# Attenuverting_LinExp_VCA.net
KiCad netlist of a schematic drawn in EAGLE
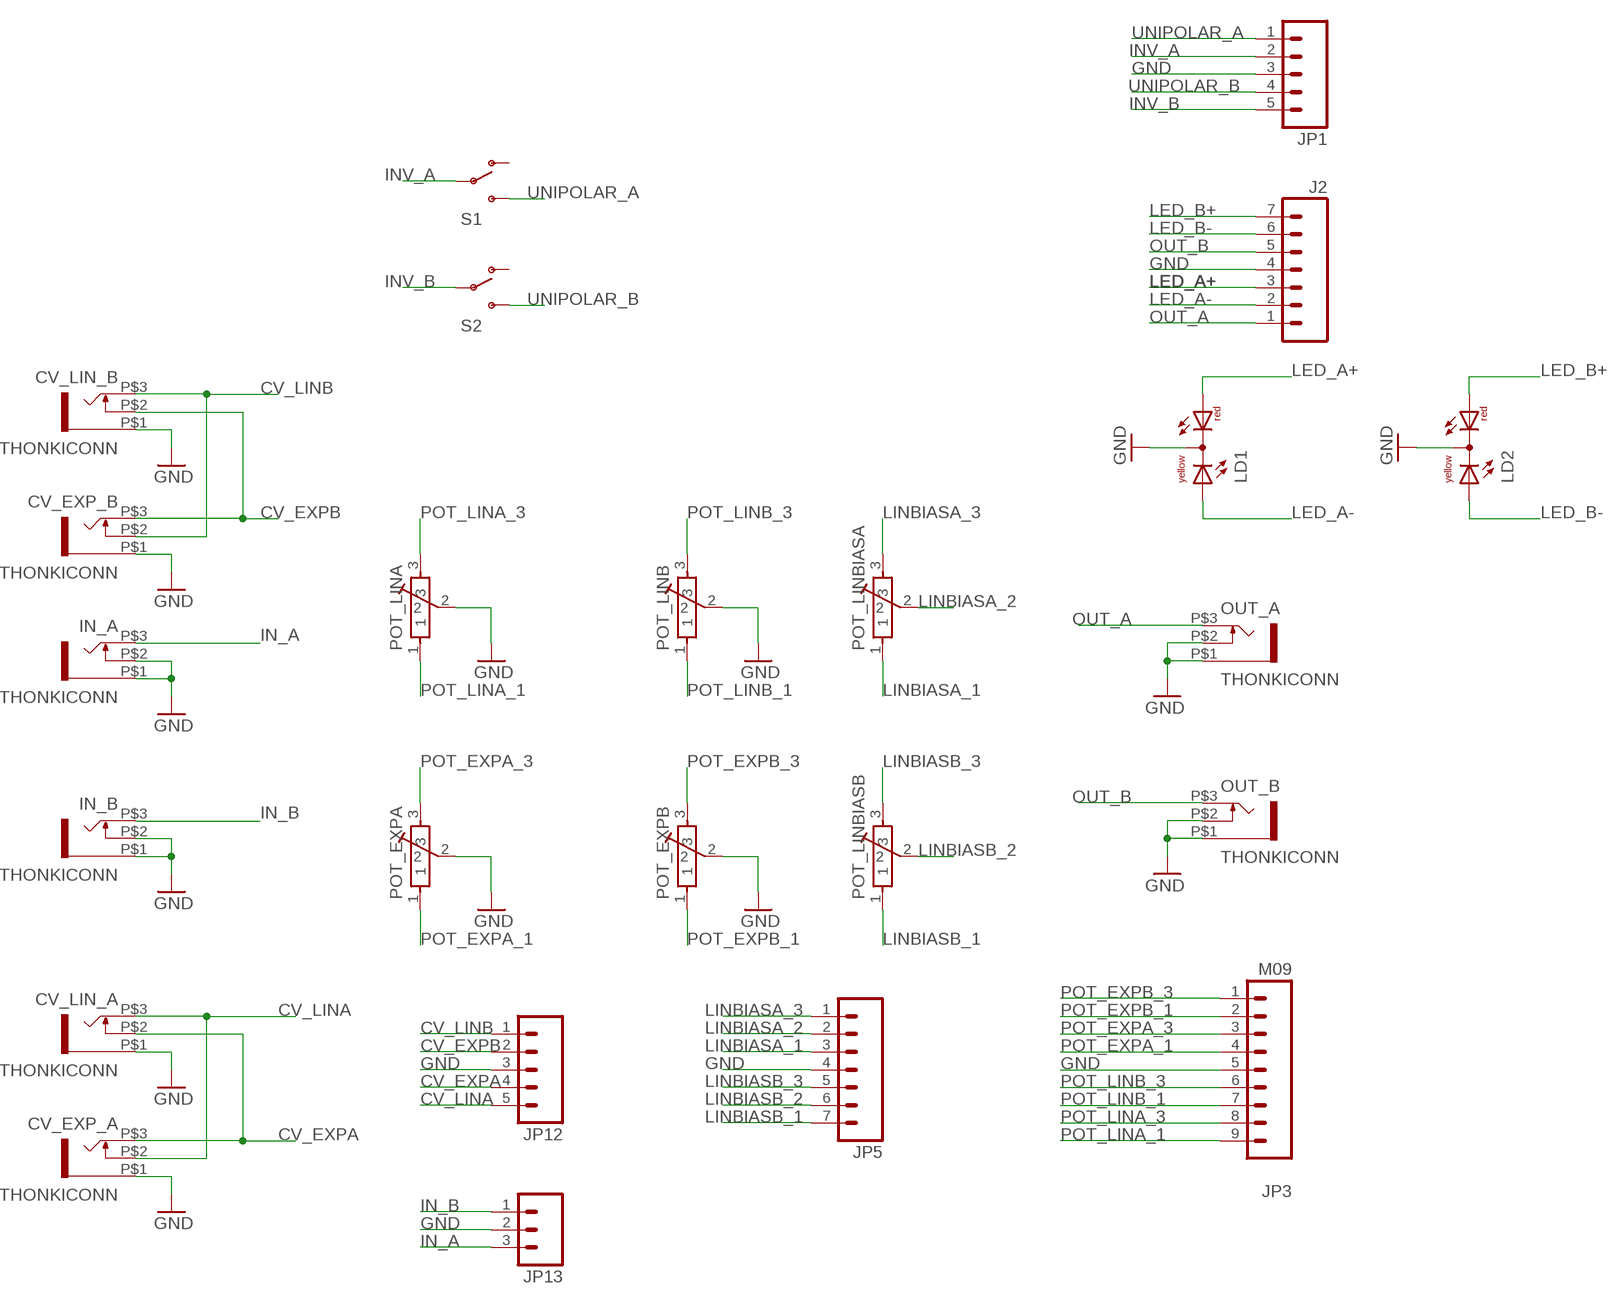
[diagram p0: schematic, sheet 1]
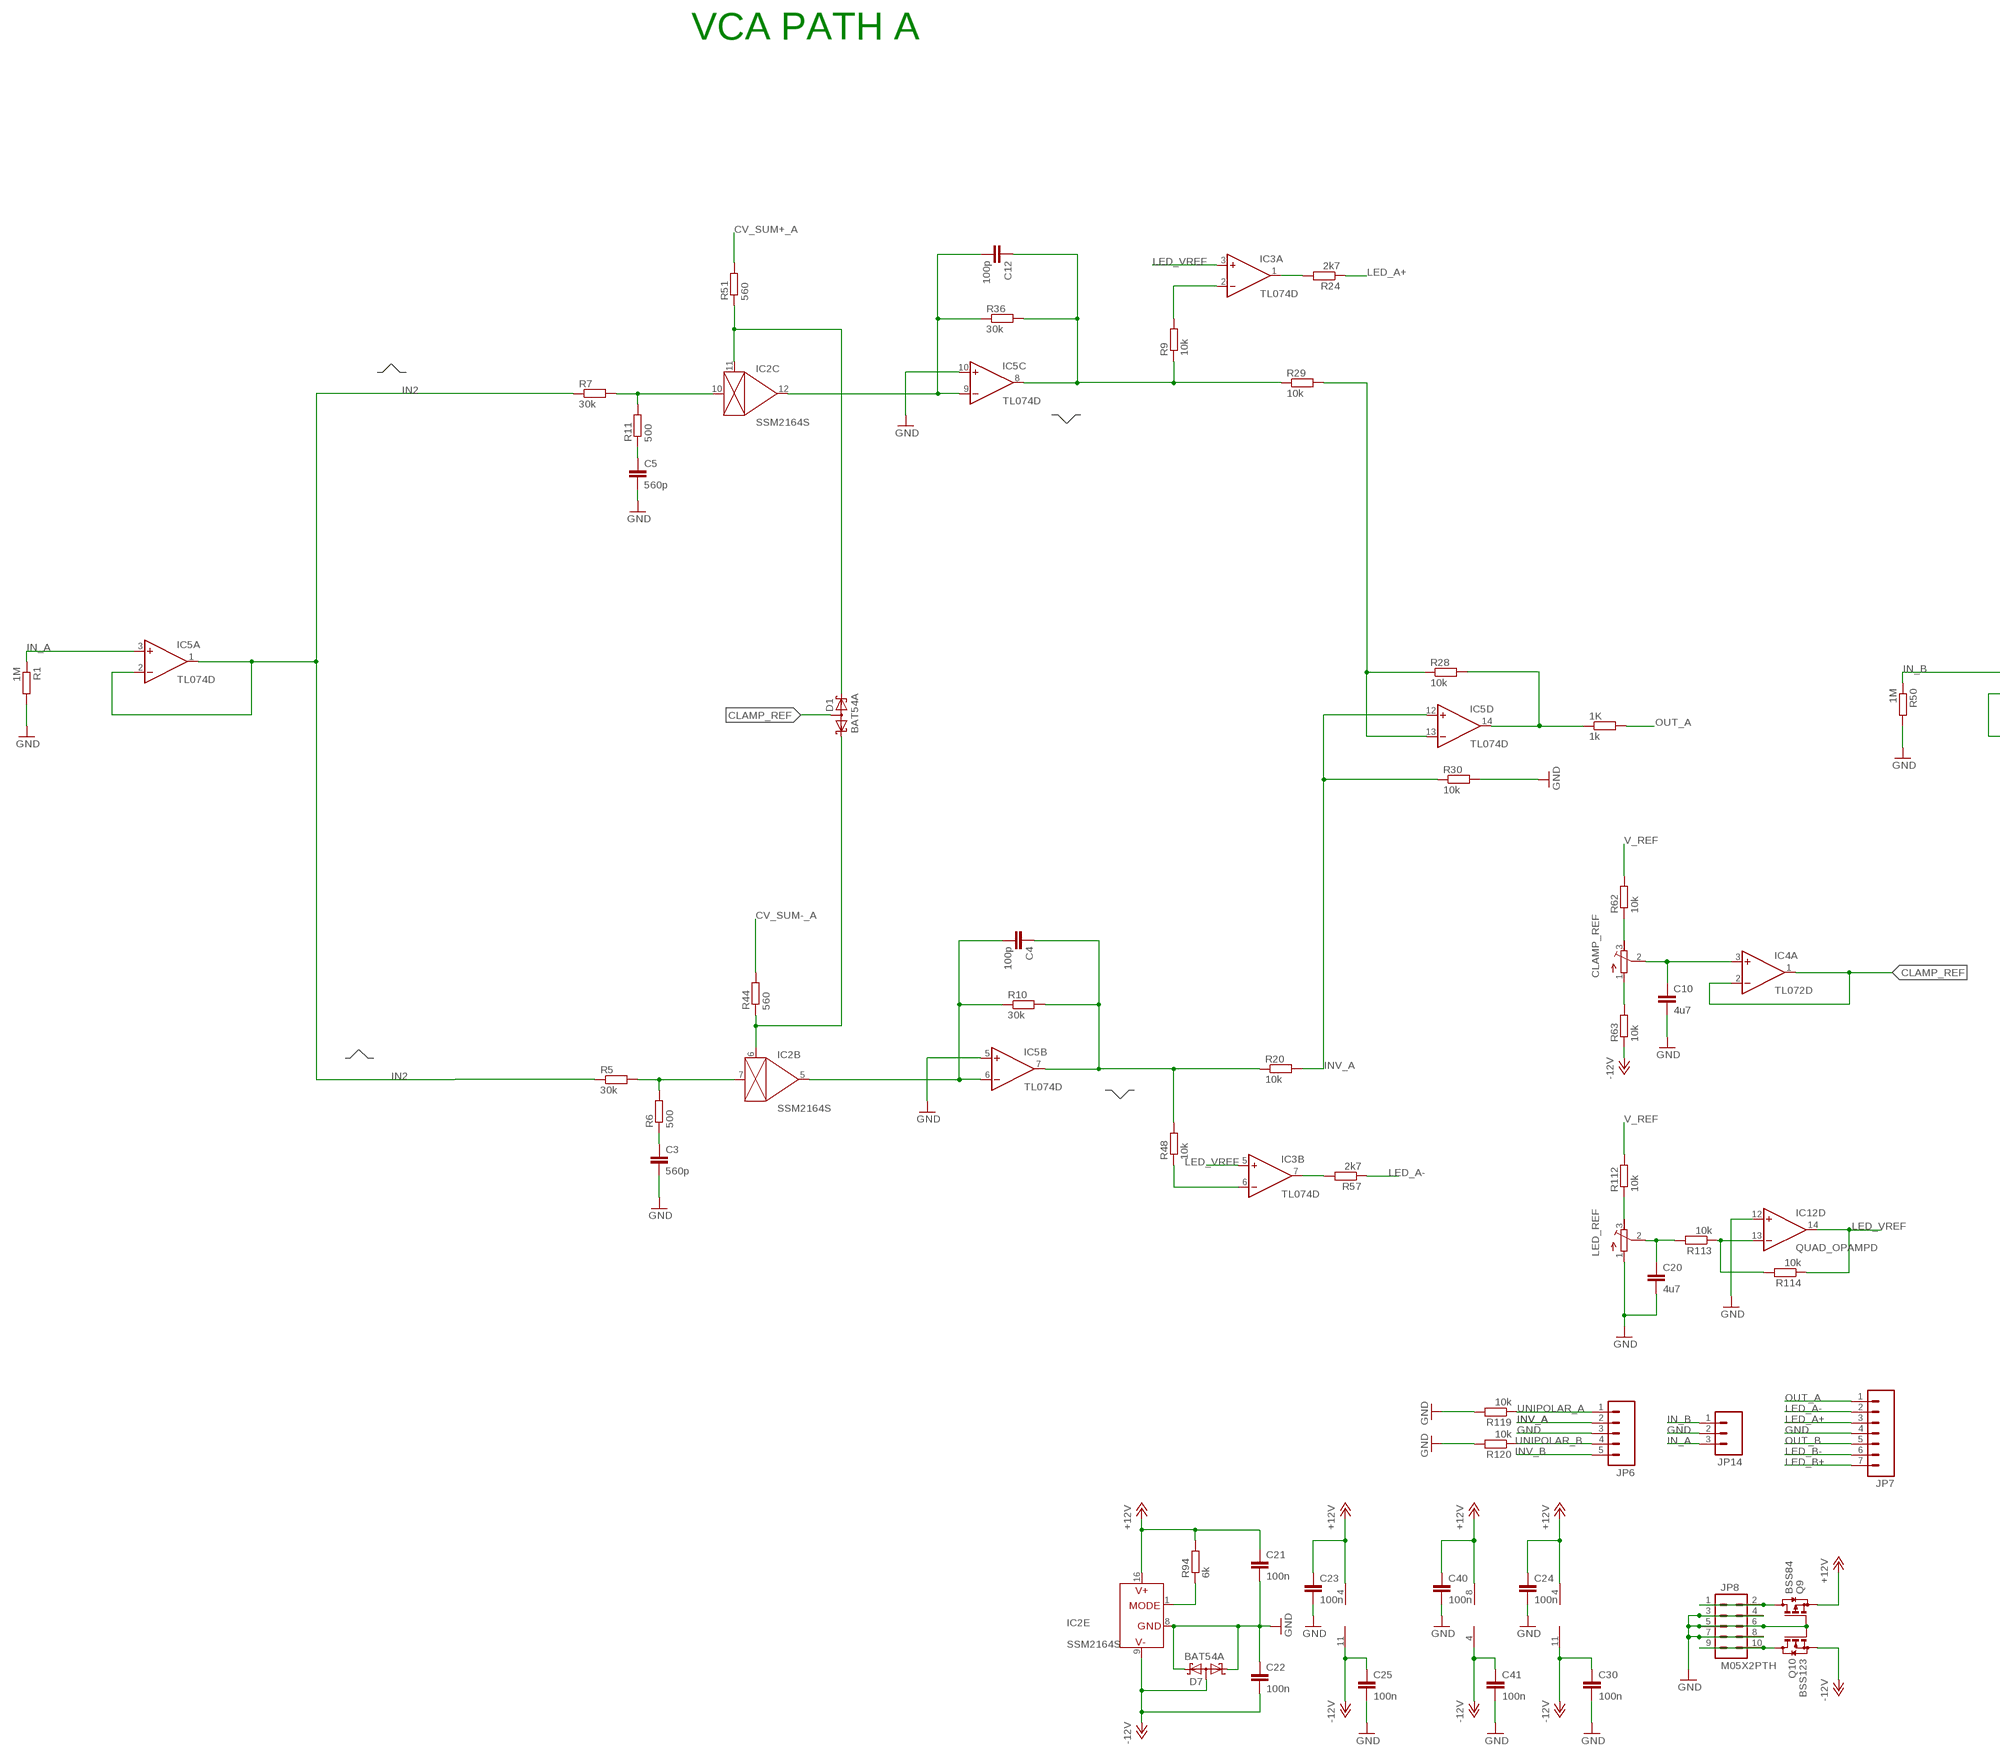
[diagram p1: schematic, sheet 2, part 1 of 2]
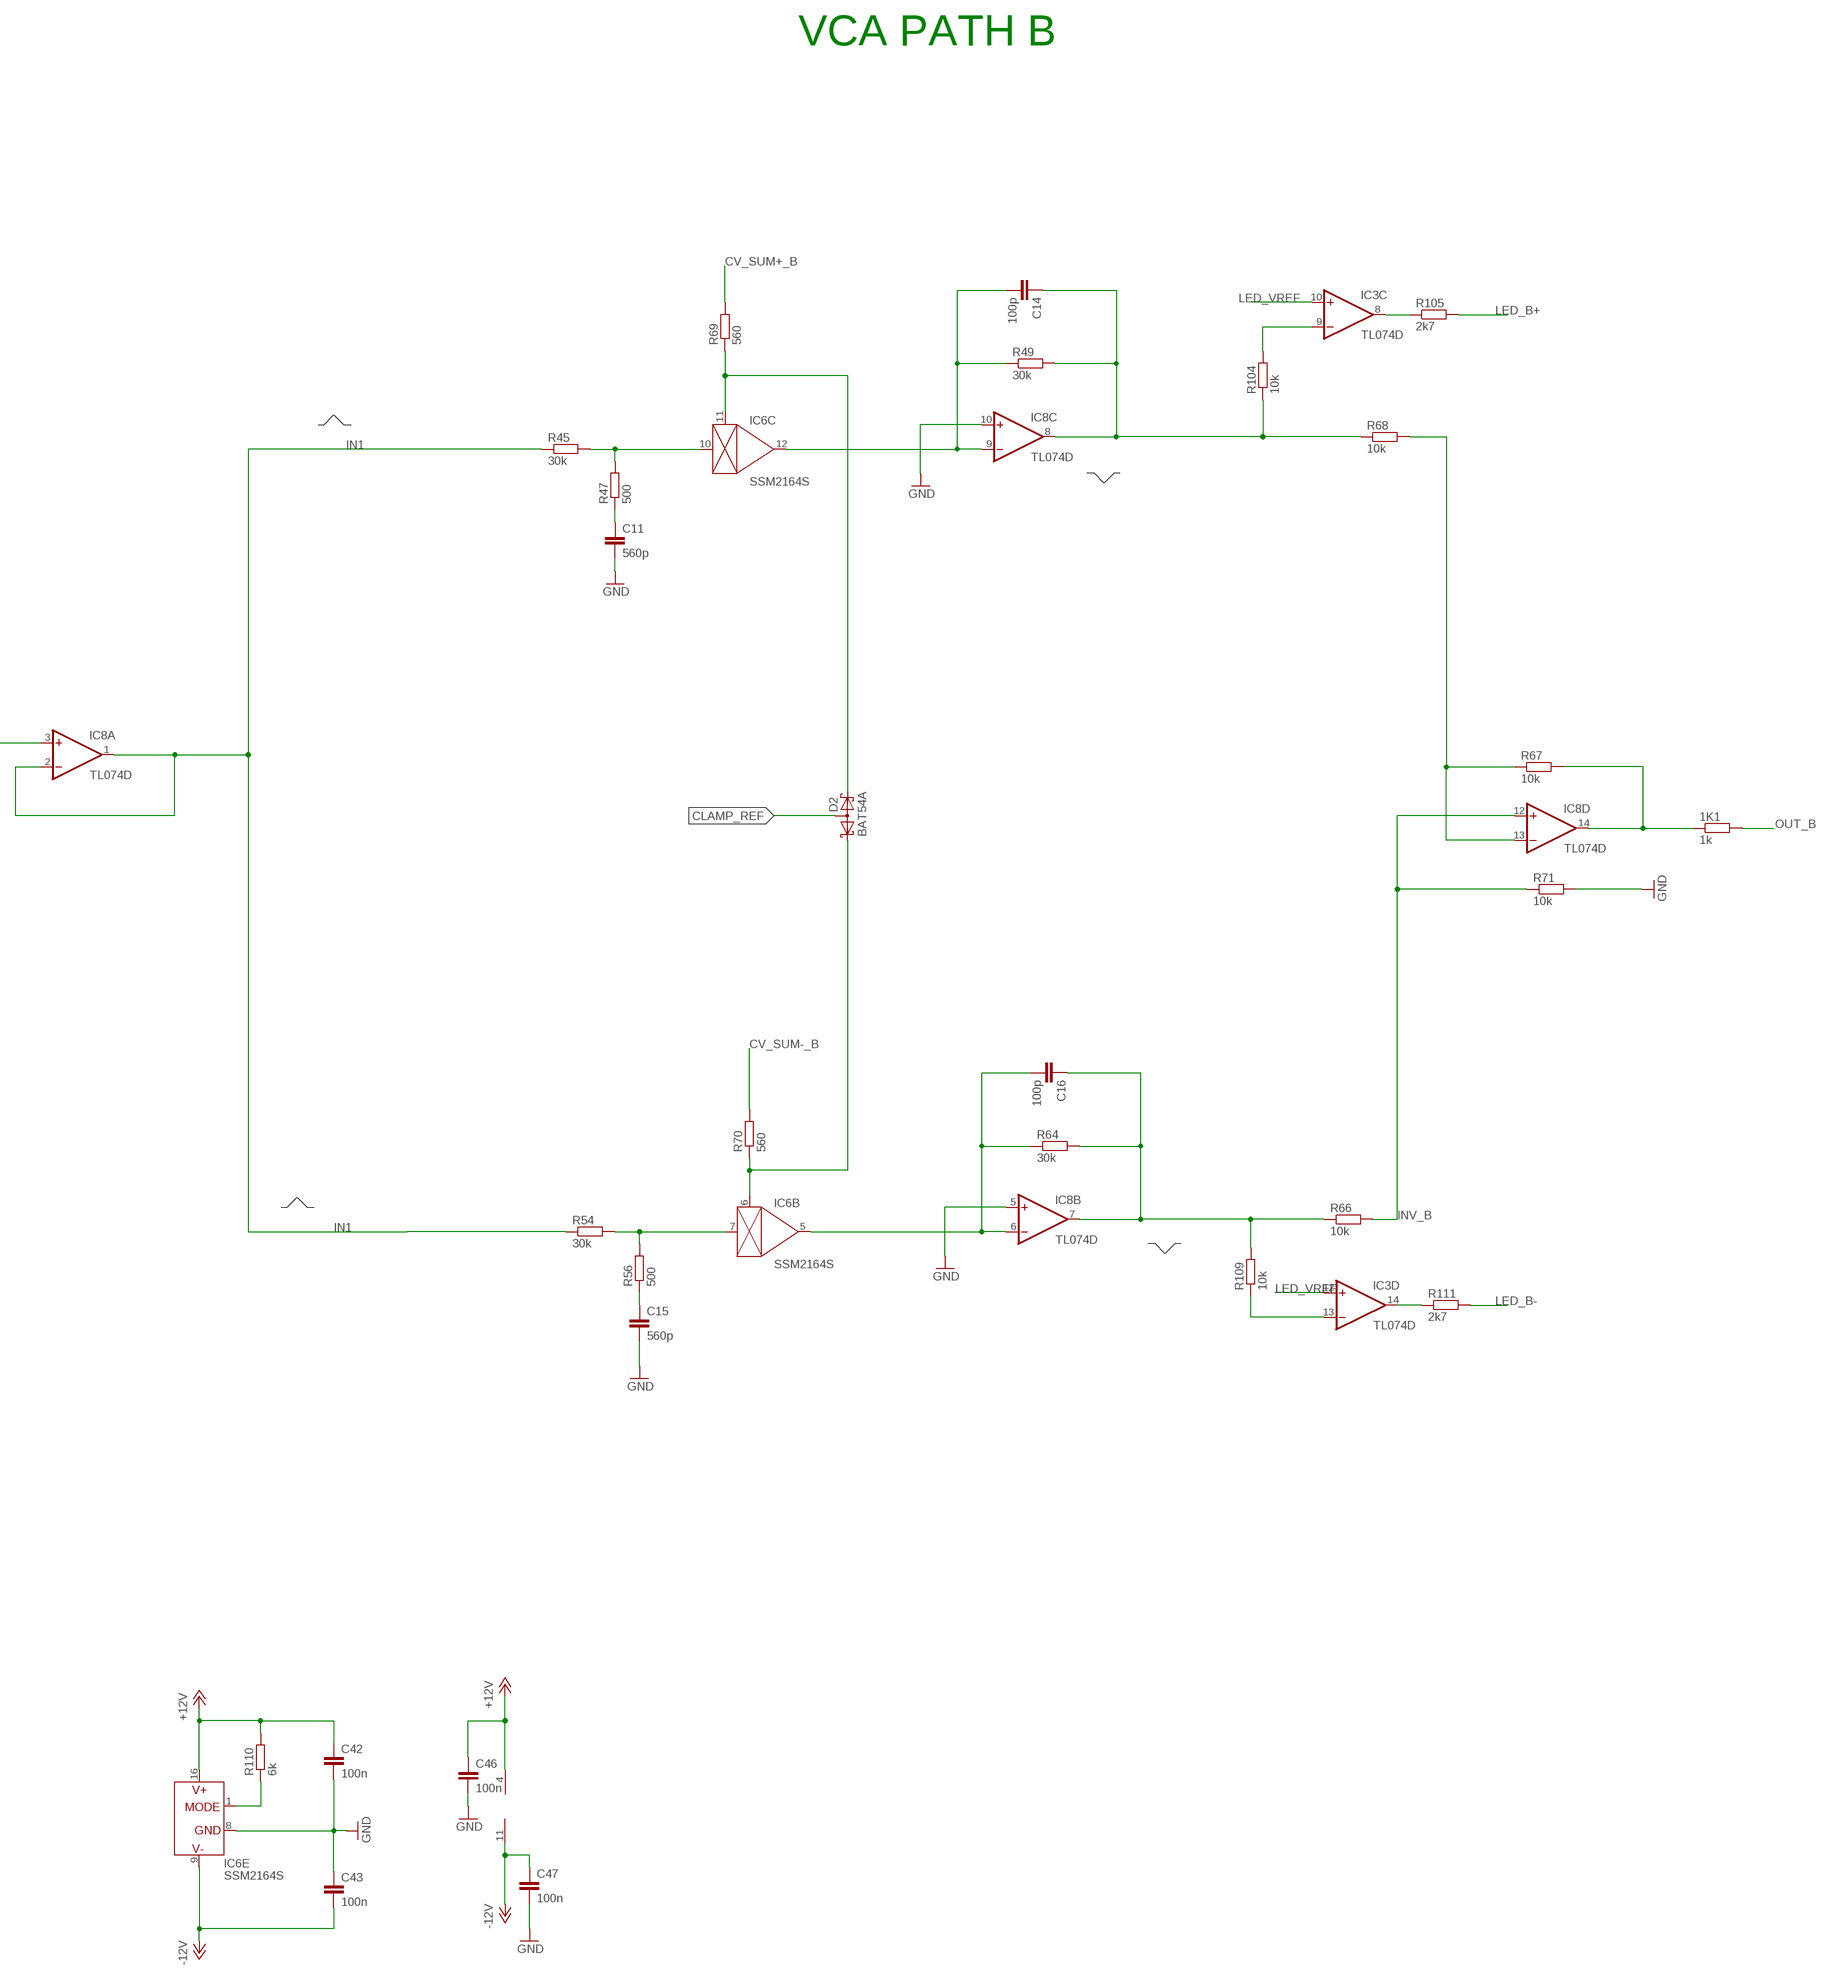
[diagram p2: schematic, sheet 2, part 2 of 2]
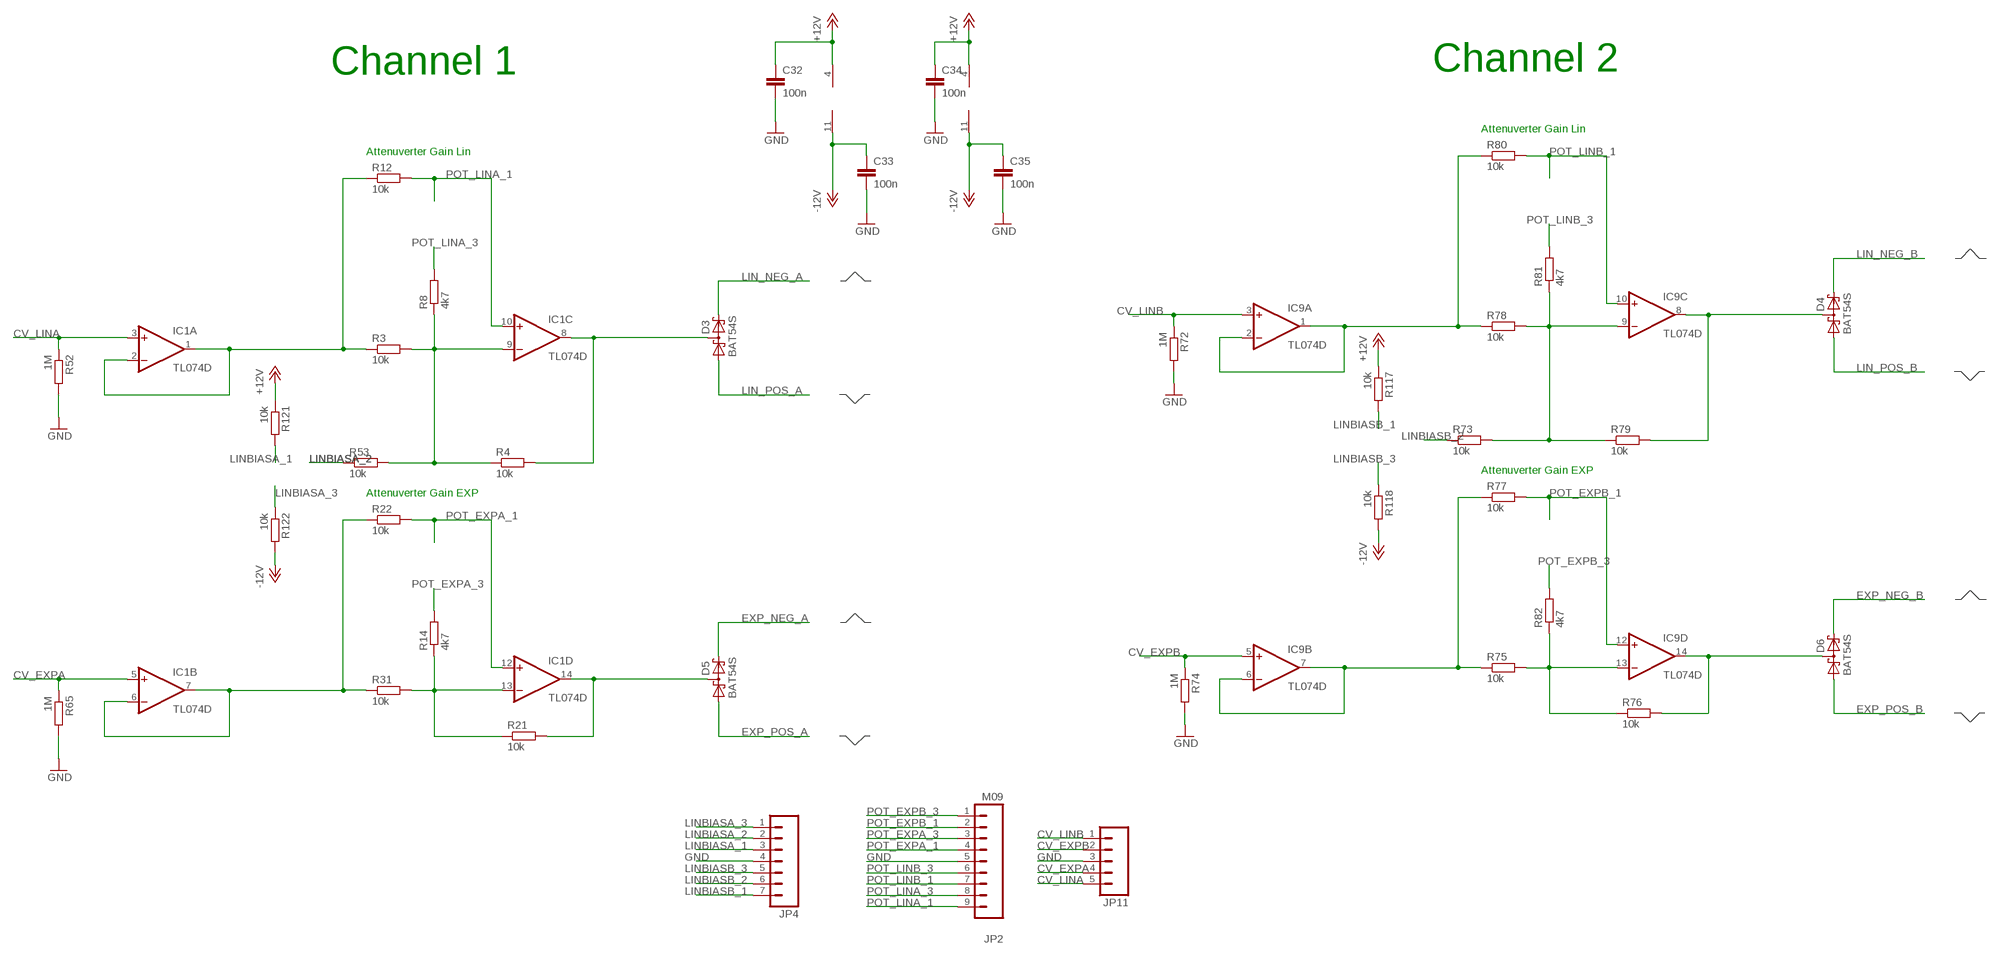
[diagram p3: schematic, sheet 3]
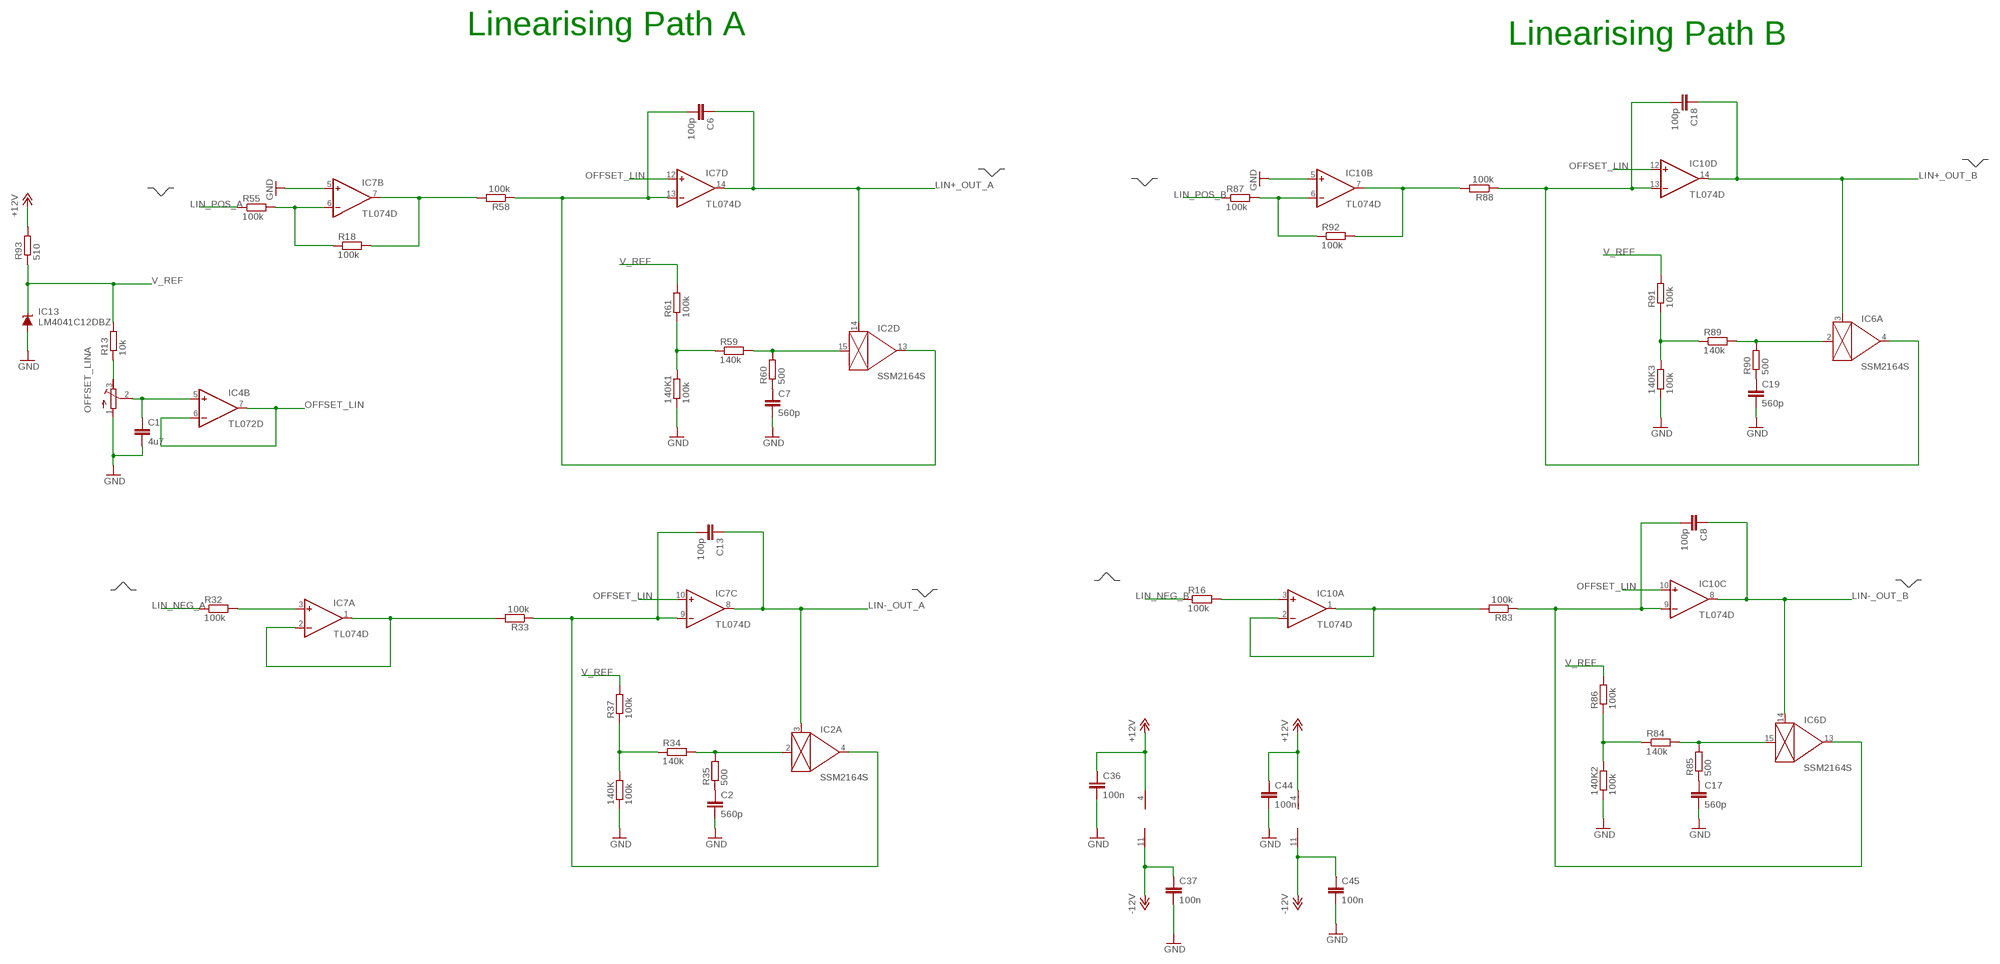
[diagram p4: schematic, sheet 4]
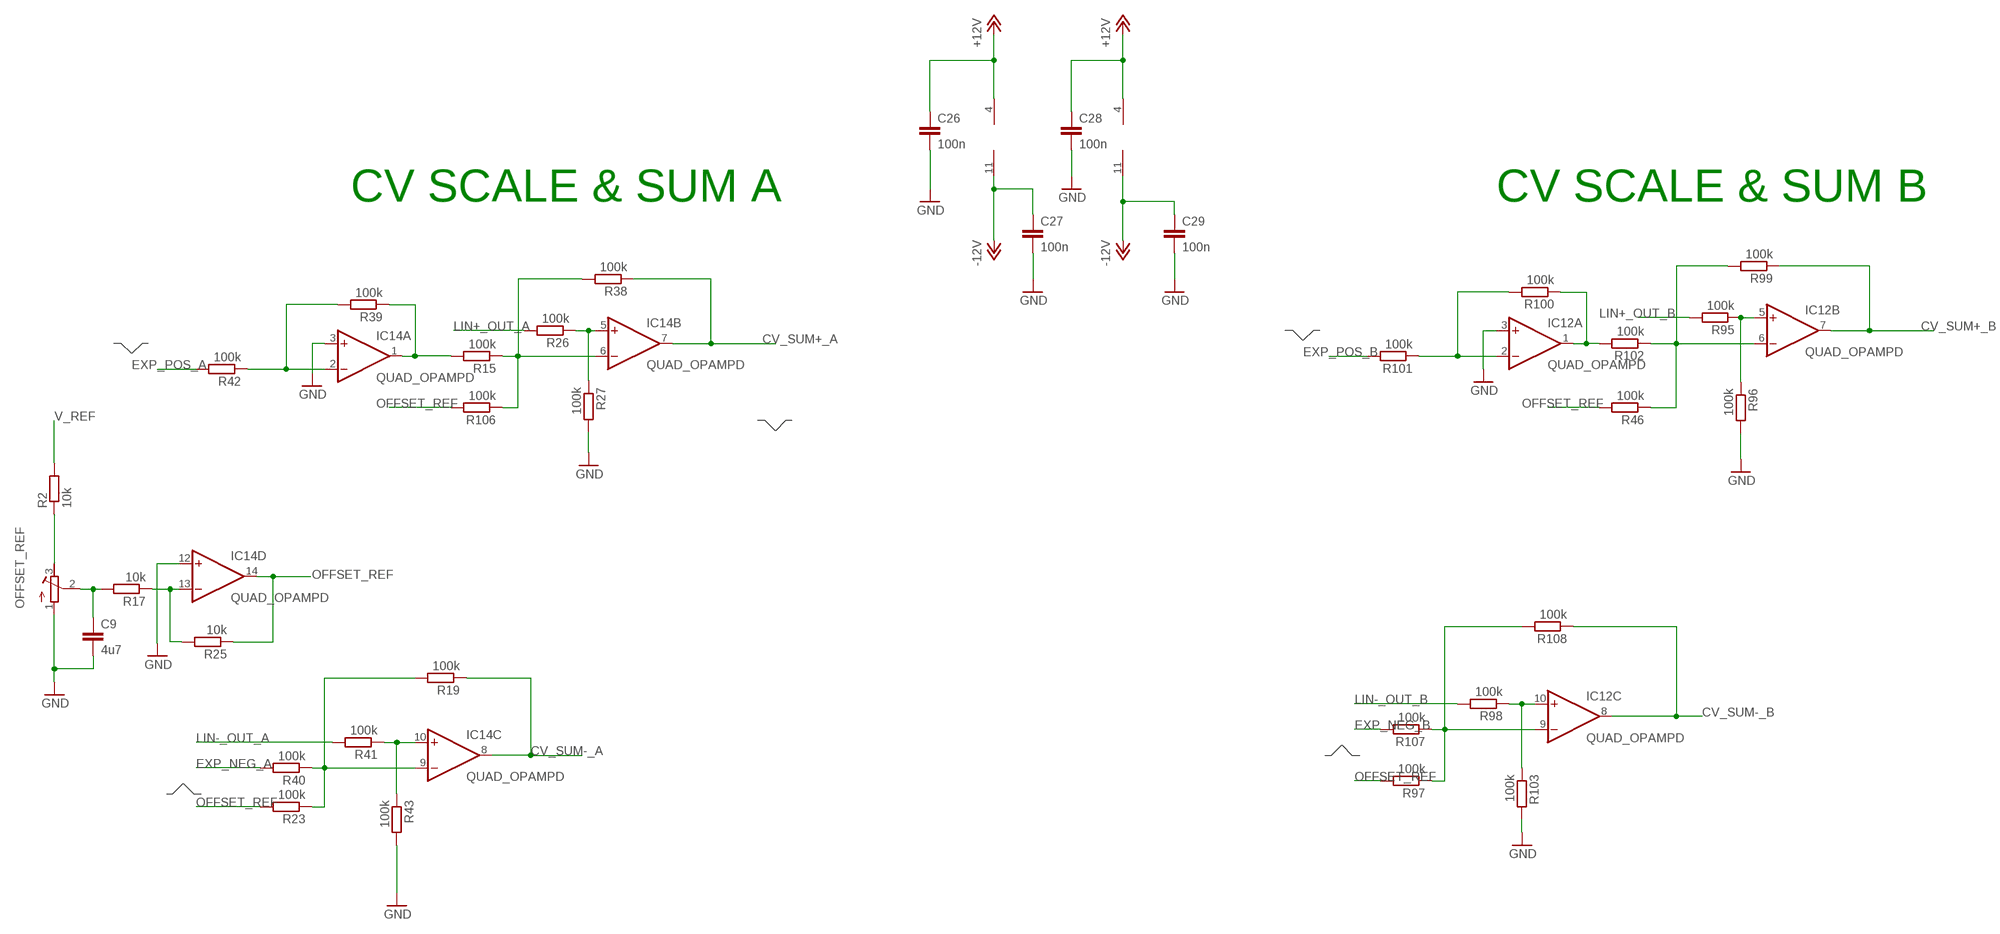
[diagram p5: schematic, sheet 5]

(export (version "E")
  (design (tool "Eeschema 10.0.6"))
  (components
    (comp (ref "CV_EXP_A")
      (value "THONKICONN")
      (footprint "eagle-import:THONKICONN")
      (libsource (lib "eagle-import") (part "THONKICONN"))
    )
    (comp (ref "CV_EXP_B")
      (value "THONKICONN")
      (footprint "eagle-import:THONKICONN")
      (libsource (lib "eagle-import") (part "THONKICONN"))
    )
    (comp (ref "CV_LIN_A")
      (value "THONKICONN")
      (footprint "eagle-import:THONKICONN")
      (libsource (lib "eagle-import") (part "THONKICONN"))
    )
    (comp (ref "CV_LIN_B")
      (value "THONKICONN")
      (footprint "eagle-import:THONKICONN")
      (libsource (lib "eagle-import") (part "THONKICONN"))
    )
    (comp (ref "IN_A")
      (value "THONKICONN")
      (footprint "eagle-import:THONKICONN")
      (libsource (lib "eagle-import") (part "THONKICONN"))
    )
    (comp (ref "IN_B")
      (value "THONKICONN")
      (footprint "eagle-import:THONKICONN")
      (libsource (lib "eagle-import") (part "THONKICONN"))
    )
    (comp (ref "J2")
      (value "M07")
      (footprint "eagle-import:1X07")
      (libsource (lib "eagle-import") (part "M07"))
    )
    (comp (ref "JP1")
      (value "M05PTH")
      (footprint "eagle-import:1X05")
      (libsource (lib "eagle-import") (part "M05PTH"))
    )
    (comp (ref "JP3")
      (value "M09")
      (footprint "eagle-import:1X09")
      (libsource (lib "eagle-import") (part "M09"))
    )
    (comp (ref "JP5")
      (value "M07")
      (footprint "eagle-import:1X07")
      (libsource (lib "eagle-import") (part "M07"))
    )
    (comp (ref "JP12")
      (value "M05PTH")
      (footprint "eagle-import:1X05")
      (libsource (lib "eagle-import") (part "M05PTH"))
    )
    (comp (ref "JP13")
      (value "M03PTH")
      (footprint "eagle-import:1X03")
      (libsource (lib "eagle-import") (part "M03PTH"))
    )
    (comp (ref "LD1")
      (value "DUOLED-RY-C")
      (footprint "eagle-import:DUOLED-C-5MM")
      (libsource (lib "eagle-import") (part "DUOLED-RY-C"))
    )
    (comp (ref "LD2")
      (value "DUOLED-RY-C")
      (footprint "eagle-import:DUOLED-C-5MM")
      (libsource (lib "eagle-import") (part "DUOLED-RY-C"))
    )
    (comp (ref "OUT_A")
      (value "THONKICONN")
      (footprint "eagle-import:THONKICONN")
      (libsource (lib "eagle-import") (part "THONKICONN"))
    )
    (comp (ref "OUT_B")
      (value "THONKICONN")
      (footprint "eagle-import:THONKICONN")
      (libsource (lib "eagle-import") (part "THONKICONN"))
    )
    (comp (ref "POT_EXPA")
      (value "POT-ALPS-RK09L1140")
      (footprint "eagle-import:POT-ALPS-RK09L1140")
      (libsource (lib "eagle-import") (part "POT-ALPS-RK09L1140"))
    )
    (comp (ref "POT_EXPB")
      (value "POT-ALPS-RK09L1140")
      (footprint "eagle-import:POT-ALPS-RK09L1140")
      (libsource (lib "eagle-import") (part "POT-ALPS-RK09L1140"))
    )
    (comp (ref "POT_LINA")
      (value "POT-ALPS-RK09L1140")
      (footprint "eagle-import:POT-ALPS-RK09L1140")
      (libsource (lib "eagle-import") (part "POT-ALPS-RK09L1140"))
    )
    (comp (ref "POT_LINB")
      (value "POT-ALPS-RK09L1140")
      (footprint "eagle-import:POT-ALPS-RK09L1140")
      (libsource (lib "eagle-import") (part "POT-ALPS-RK09L1140"))
    )
    (comp (ref "POT_LINBIASA")
      (value "POT-ALPS-RK09L1140")
      (footprint "eagle-import:POT-ALPS-RK09L1140")
      (libsource (lib "eagle-import") (part "POT-ALPS-RK09L1140"))
    )
    (comp (ref "POT_LINBIASB")
      (value "POT-ALPS-RK09L1140")
      (footprint "eagle-import:POT-ALPS-RK09L1140")
      (libsource (lib "eagle-import") (part "POT-ALPS-RK09L1140"))
    )
    (comp (ref "S1")
      (value "SWITCH-SPST")
      (footprint "eagle-import:SWITCH-SPDT-SALECOM-T8014")
      (libsource (lib "eagle-import") (part "SWITCH-SPST"))
    )
    (comp (ref "S2")
      (value "SWITCH-SPST")
      (footprint "eagle-import:SWITCH-SPDT-SALECOM-T8014")
      (libsource (lib "eagle-import") (part "SWITCH-SPST"))
    )
    (comp (ref "140K")
      (value "100k")
      (footprint "eagle-import:0603")
      (libsource (lib "eagle-import") (part "R-EU_0603"))
    )
    (comp (ref "140K1")
      (value "100k")
      (footprint "eagle-import:0603")
      (libsource (lib "eagle-import") (part "R-EU_0603"))
    )
    (comp (ref "140K2")
      (value "100k")
      (footprint "eagle-import:0603")
      (libsource (lib "eagle-import") (part "R-EU_0603"))
    )
    (comp (ref "140K3")
      (value "100k")
      (footprint "eagle-import:0603")
      (libsource (lib "eagle-import") (part "R-EU_0603"))
    )
    (comp (ref "C1")
      (value "4u7")
      (footprint "eagle-import:C0603K")
      (libsource (lib "eagle-import") (part "resistor_C-EUC0603K"))
    )
    (comp (ref "C2")
      (value "560p")
      (footprint "eagle-import:C0603K")
      (libsource (lib "eagle-import") (part "resistor_C-EUC0603K"))
    )
    (comp (ref "C6")
      (value "100p")
      (footprint "eagle-import:C0603K")
      (libsource (lib "eagle-import") (part "resistor_C-EUC0603K"))
    )
    (comp (ref "C7")
      (value "560p")
      (footprint "eagle-import:C0603K")
      (libsource (lib "eagle-import") (part "resistor_C-EUC0603K"))
    )
    (comp (ref "C8")
      (value "100p")
      (footprint "eagle-import:C0603K")
      (libsource (lib "eagle-import") (part "resistor_C-EUC0603K"))
    )
    (comp (ref "C13")
      (value "100p")
      (footprint "eagle-import:C0603K")
      (libsource (lib "eagle-import") (part "resistor_C-EUC0603K"))
    )
    (comp (ref "C17")
      (value "560p")
      (footprint "eagle-import:C0603K")
      (libsource (lib "eagle-import") (part "resistor_C-EUC0603K"))
    )
    (comp (ref "C18")
      (value "100p")
      (footprint "eagle-import:C0603K")
      (libsource (lib "eagle-import") (part "resistor_C-EUC0603K"))
    )
    (comp (ref "C19")
      (value "560p")
      (footprint "eagle-import:C0603K")
      (libsource (lib "eagle-import") (part "resistor_C-EUC0603K"))
    )
    (comp (ref "C36")
      (value "100n")
      (footprint "eagle-import:C0603K")
      (libsource (lib "eagle-import") (part "rcl@1_C-EUC0603K"))
    )
    (comp (ref "C37")
      (value "100n")
      (footprint "eagle-import:C0603K")
      (libsource (lib "eagle-import") (part "rcl@1_C-EUC0603K"))
    )
    (comp (ref "C44")
      (value "100n")
      (footprint "eagle-import:C0603K")
      (libsource (lib "eagle-import") (part "rcl@1_C-EUC0603K"))
    )
    (comp (ref "C45")
      (value "100n")
      (footprint "eagle-import:C0603K")
      (libsource (lib "eagle-import") (part "rcl@1_C-EUC0603K"))
    )
    (comp (ref "IC2")
      (value "SSM2164S")
      (footprint "eagle-import:SOIC16N")
      (fields (field (name "OC_FARNELL") "unknown"))
      (libsource (lib "eagle-import") (part "SSM2164S"))
    )
    (comp (ref "IC4")
      (value "TL072D")
      (footprint "eagle-import:SO08")
      (libsource (lib "eagle-import") (part "TL072D"))
    )
    (comp (ref "IC6")
      (value "SSM2164S")
      (footprint "eagle-import:SOIC16N")
      (fields (field (name "OC_FARNELL") "unknown"))
      (libsource (lib "eagle-import") (part "SSM2164S"))
    )
    (comp (ref "IC7")
      (value "TL074D")
      (footprint "eagle-import:SO14")
      (fields (field (name "OC_FARNELL") "unknown"))
      (libsource (lib "eagle-import") (part "TL074D"))
    )
    (comp (ref "IC10")
      (value "TL074D")
      (footprint "eagle-import:SO14")
      (fields (field (name "OC_FARNELL") "unknown"))
      (libsource (lib "eagle-import") (part "TL074D"))
    )
    (comp (ref "IC13")
      (value "LM4041C12DBZ")
      (footprint "eagle-import:DBZ_R-PDSO-G3")
      (fields (field (name "MF") "TEXAS INSTRUMENT CONNECTORS") (field (name "MPN") "LM4041C12QDBZT"))
      (libsource (lib "eagle-import") (part "LM4041DBZC12"))
    )
    (comp (ref "OFFSET_LINA")
      (value "R-TRIMM64W")
      (footprint "eagle-import:RTRIM64W")
      (libsource (lib "eagle-import") (part "R-TRIMM64W"))
    )
    (comp (ref "R13")
      (value "10k")
      (footprint "eagle-import:0603")
      (libsource (lib "eagle-import") (part "R-EU_0603"))
    )
    (comp (ref "R16")
      (value "100k")
      (footprint "eagle-import:0603")
      (libsource (lib "eagle-import") (part "R-EU_0603"))
    )
    (comp (ref "R18")
      (value "100k")
      (footprint "eagle-import:0603")
      (libsource (lib "eagle-import") (part "R-EU_0603"))
    )
    (comp (ref "R32")
      (value "100k")
      (footprint "eagle-import:0603")
      (libsource (lib "eagle-import") (part "R-EU_0603"))
    )
    (comp (ref "R33")
      (value "100k")
      (footprint "eagle-import:0603")
      (libsource (lib "eagle-import") (part "R-EU_0603"))
    )
    (comp (ref "R34")
      (value "140k")
      (footprint "eagle-import:0603")
      (libsource (lib "eagle-import") (part "R-EU_0603"))
    )
    (comp (ref "R35")
      (value "500")
      (footprint "eagle-import:0603")
      (libsource (lib "eagle-import") (part "R-EU_0603"))
    )
    (comp (ref "R37")
      (value "100k")
      (footprint "eagle-import:0603")
      (libsource (lib "eagle-import") (part "R-EU_0603"))
    )
    (comp (ref "R55")
      (value "100k")
      (footprint "eagle-import:0603")
      (libsource (lib "eagle-import") (part "R-EU_0603"))
    )
    (comp (ref "R58")
      (value "100k")
      (footprint "eagle-import:0603")
      (libsource (lib "eagle-import") (part "R-EU_0603"))
    )
    (comp (ref "R59")
      (value "140k")
      (footprint "eagle-import:0603")
      (libsource (lib "eagle-import") (part "R-EU_0603"))
    )
    (comp (ref "R60")
      (value "500")
      (footprint "eagle-import:0603")
      (libsource (lib "eagle-import") (part "R-EU_0603"))
    )
    (comp (ref "R61")
      (value "100k")
      (footprint "eagle-import:0603")
      (libsource (lib "eagle-import") (part "R-EU_0603"))
    )
    (comp (ref "R83")
      (value "100k")
      (footprint "eagle-import:0603")
      (libsource (lib "eagle-import") (part "R-EU_0603"))
    )
    (comp (ref "R84")
      (value "140k")
      (footprint "eagle-import:0603")
      (libsource (lib "eagle-import") (part "R-EU_0603"))
    )
    (comp (ref "R85")
      (value "500")
      (footprint "eagle-import:0603")
      (libsource (lib "eagle-import") (part "R-EU_0603"))
    )
    (comp (ref "R86")
      (value "100k")
      (footprint "eagle-import:0603")
      (libsource (lib "eagle-import") (part "R-EU_0603"))
    )
    (comp (ref "R87")
      (value "100k")
      (footprint "eagle-import:0603")
      (libsource (lib "eagle-import") (part "R-EU_0603"))
    )
    (comp (ref "R88")
      (value "100k")
      (footprint "eagle-import:0603")
      (libsource (lib "eagle-import") (part "R-EU_0603"))
    )
    (comp (ref "R89")
      (value "140k")
      (footprint "eagle-import:0603")
      (libsource (lib "eagle-import") (part "R-EU_0603"))
    )
    (comp (ref "R90")
      (value "500")
      (footprint "eagle-import:0603")
      (libsource (lib "eagle-import") (part "R-EU_0603"))
    )
    (comp (ref "R91")
      (value "100k")
      (footprint "eagle-import:0603")
      (libsource (lib "eagle-import") (part "R-EU_0603"))
    )
    (comp (ref "R92")
      (value "100k")
      (footprint "eagle-import:0603")
      (libsource (lib "eagle-import") (part "R-EU_0603"))
    )
    (comp (ref "R93")
      (value "510")
      (footprint "eagle-import:0603")
      (libsource (lib "eagle-import") (part "R-EU_0603"))
    )
    (comp (ref "C9")
      (value "4u7")
      (footprint "eagle-import:C0603K")
      (libsource (lib "eagle-import") (part "resistor_C-EUC0603K"))
    )
    (comp (ref "C26")
      (value "100n")
      (footprint "eagle-import:C0603K")
      (libsource (lib "eagle-import") (part "C-EUC0603K"))
    )
    (comp (ref "C27")
      (value "100n")
      (footprint "eagle-import:C0603K")
      (libsource (lib "eagle-import") (part "C-EUC0603K"))
    )
    (comp (ref "C28")
      (value "100n")
      (footprint "eagle-import:C0603K")
      (libsource (lib "eagle-import") (part "C-EUC0603K"))
    )
    (comp (ref "C29")
      (value "100n")
      (footprint "eagle-import:C0603K")
      (libsource (lib "eagle-import") (part "C-EUC0603K"))
    )
    (comp (ref "IC12")
      (value "QUAD_OPAMPD")
      (footprint "eagle-import:SO14")
      (libsource (lib "eagle-import") (part "QUAD_OPAMPD"))
    )
    (comp (ref "IC14")
      (value "QUAD_OPAMPD")
      (footprint "eagle-import:SO14")
      (libsource (lib "eagle-import") (part "QUAD_OPAMPD"))
    )
    (comp (ref "OFFSET_REF")
      (value "R-TRIMM64W")
      (footprint "eagle-import:RTRIM64W")
      (libsource (lib "eagle-import") (part "R-TRIMM64W"))
    )
    (comp (ref "R2")
      (value "10k")
      (footprint "eagle-import:0603")
      (libsource (lib "eagle-import") (part "R-EU_0603"))
    )
    (comp (ref "R15")
      (value "100k")
      (footprint "eagle-import:0603")
      (libsource (lib "eagle-import") (part "R-EU_0603"))
    )
    (comp (ref "R17")
      (value "10k")
      (footprint "eagle-import:0603")
      (libsource (lib "eagle-import") (part "R-EU_0603"))
    )
    (comp (ref "R19")
      (value "100k")
      (footprint "eagle-import:0603")
      (libsource (lib "eagle-import") (part "R-EU_0603"))
    )
    (comp (ref "R23")
      (value "100k")
      (footprint "eagle-import:0603")
      (libsource (lib "eagle-import") (part "R-EU_0603"))
    )
    (comp (ref "R25")
      (value "10k")
      (footprint "eagle-import:0603")
      (libsource (lib "eagle-import") (part "R-EU_0603"))
    )
    (comp (ref "R26")
      (value "100k")
      (footprint "eagle-import:0603")
      (libsource (lib "eagle-import") (part "R-EU_0603"))
    )
    (comp (ref "R27")
      (value "100k")
      (footprint "eagle-import:0603")
      (libsource (lib "eagle-import") (part "R-EU_0603"))
    )
    (comp (ref "R38")
      (value "100k")
      (footprint "eagle-import:0603")
      (libsource (lib "eagle-import") (part "R-EU_0603"))
    )
    (comp (ref "R39")
      (value "100k")
      (footprint "eagle-import:0603")
      (libsource (lib "eagle-import") (part "R-EU_0603"))
    )
    (comp (ref "R40")
      (value "100k")
      (footprint "eagle-import:0603")
      (libsource (lib "eagle-import") (part "R-EU_0603"))
    )
    (comp (ref "R41")
      (value "100k")
      (footprint "eagle-import:0603")
      (libsource (lib "eagle-import") (part "R-EU_0603"))
    )
    (comp (ref "R42")
      (value "100k")
      (footprint "eagle-import:0603")
      (libsource (lib "eagle-import") (part "R-EU_0603"))
    )
    (comp (ref "R43")
      (value "100k")
      (footprint "eagle-import:0603")
      (libsource (lib "eagle-import") (part "R-EU_0603"))
    )
    (comp (ref "R46")
      (value "100k")
      (footprint "eagle-import:0603")
      (libsource (lib "eagle-import") (part "R-EU_0603"))
    )
    (comp (ref "R95")
      (value "100k")
      (footprint "eagle-import:0603")
      (libsource (lib "eagle-import") (part "R-EU_0603"))
    )
    (comp (ref "R96")
      (value "100k")
      (footprint "eagle-import:0603")
      (libsource (lib "eagle-import") (part "R-EU_0603"))
    )
    (comp (ref "R97")
      (value "100k")
      (footprint "eagle-import:0603")
      (libsource (lib "eagle-import") (part "R-EU_0603"))
    )
    (comp (ref "R98")
      (value "100k")
      (footprint "eagle-import:0603")
      (libsource (lib "eagle-import") (part "R-EU_0603"))
    )
    (comp (ref "R99")
      (value "100k")
      (footprint "eagle-import:0603")
      (libsource (lib "eagle-import") (part "R-EU_0603"))
    )
    (comp (ref "R100")
      (value "100k")
      (footprint "eagle-import:0603")
      (libsource (lib "eagle-import") (part "R-EU_0603"))
    )
    (comp (ref "R101")
      (value "100k")
      (footprint "eagle-import:0603")
      (libsource (lib "eagle-import") (part "R-EU_0603"))
    )
    (comp (ref "R102")
      (value "100k")
      (footprint "eagle-import:0603")
      (libsource (lib "eagle-import") (part "R-EU_0603"))
    )
    (comp (ref "R103")
      (value "100k")
      (footprint "eagle-import:0603")
      (libsource (lib "eagle-import") (part "R-EU_0603"))
    )
    (comp (ref "R106")
      (value "100k")
      (footprint "eagle-import:0603")
      (libsource (lib "eagle-import") (part "R-EU_0603"))
    )
    (comp (ref "R107")
      (value "100k")
      (footprint "eagle-import:0603")
      (libsource (lib "eagle-import") (part "R-EU_0603"))
    )
    (comp (ref "R108")
      (value "100k")
      (footprint "eagle-import:0603")
      (libsource (lib "eagle-import") (part "R-EU_0603"))
    )
    (comp (ref "C32")
      (value "100n")
      (footprint "eagle-import:C0603K")
      (libsource (lib "eagle-import") (part "C-EUC0603K"))
    )
    (comp (ref "C33")
      (value "100n")
      (footprint "eagle-import:C0603K")
      (libsource (lib "eagle-import") (part "C-EUC0603K"))
    )
    (comp (ref "C34")
      (value "100n")
      (footprint "eagle-import:C0603K")
      (libsource (lib "eagle-import") (part "C-EUC0603K"))
    )
    (comp (ref "C35")
      (value "100n")
      (footprint "eagle-import:C0603K")
      (libsource (lib "eagle-import") (part "C-EUC0603K"))
    )
    (comp (ref "D3")
      (value "BAT54S")
      (footprint "eagle-import:SOT23")
      (libsource (lib "eagle-import") (part "BAT54S"))
    )
    (comp (ref "D4")
      (value "BAT54S")
      (footprint "eagle-import:SOT23")
      (libsource (lib "eagle-import") (part "BAT54S"))
    )
    (comp (ref "D5")
      (value "BAT54S")
      (footprint "eagle-import:SOT23")
      (libsource (lib "eagle-import") (part "BAT54S"))
    )
    (comp (ref "D6")
      (value "BAT54S")
      (footprint "eagle-import:SOT23")
      (libsource (lib "eagle-import") (part "BAT54S"))
    )
    (comp (ref "IC1")
      (value "TL074D")
      (footprint "eagle-import:SO14")
      (fields (field (name "OC_FARNELL") "unknown"))
      (libsource (lib "eagle-import") (part "TL074D"))
    )
    (comp (ref "IC9")
      (value "TL074D")
      (footprint "eagle-import:SO14")
      (fields (field (name "OC_FARNELL") "unknown"))
      (libsource (lib "eagle-import") (part "TL074D"))
    )
    (comp (ref "JP2")
      (value "M09")
      (footprint "eagle-import:1X09")
      (libsource (lib "eagle-import") (part "M09"))
    )
    (comp (ref "JP4")
      (value "M07")
      (footprint "eagle-import:1X07")
      (libsource (lib "eagle-import") (part "M07"))
    )
    (comp (ref "JP11")
      (value "M05PTH")
      (footprint "eagle-import:1X05")
      (libsource (lib "eagle-import") (part "M05PTH"))
    )
    (comp (ref "R3")
      (value "10k")
      (footprint "eagle-import:0603")
      (libsource (lib "eagle-import") (part "R-EU_0603"))
    )
    (comp (ref "R4")
      (value "10k")
      (footprint "eagle-import:0603")
      (libsource (lib "eagle-import") (part "R-EU_0603"))
    )
    (comp (ref "R8")
      (value "4k7")
      (footprint "eagle-import:0603")
      (libsource (lib "eagle-import") (part "R-EU_0603"))
    )
    (comp (ref "R12")
      (value "10k")
      (footprint "eagle-import:0603")
      (libsource (lib "eagle-import") (part "R-EU_0603"))
    )
    (comp (ref "R14")
      (value "4k7")
      (footprint "eagle-import:0603")
      (libsource (lib "eagle-import") (part "R-EU_0603"))
    )
    (comp (ref "R21")
      (value "10k")
      (footprint "eagle-import:0603")
      (libsource (lib "eagle-import") (part "R-EU_0603"))
    )
    (comp (ref "R22")
      (value "10k")
      (footprint "eagle-import:0603")
      (libsource (lib "eagle-import") (part "R-EU_0603"))
    )
    (comp (ref "R31")
      (value "10k")
      (footprint "eagle-import:0603")
      (libsource (lib "eagle-import") (part "R-EU_0603"))
    )
    (comp (ref "R52")
      (value "1M")
      (footprint "eagle-import:0603")
      (libsource (lib "eagle-import") (part "R-EU_0603"))
    )
    (comp (ref "R53")
      (value "10k")
      (footprint "eagle-import:0603")
      (libsource (lib "eagle-import") (part "R-EU_0603"))
    )
    (comp (ref "R65")
      (value "1M")
      (footprint "eagle-import:0603")
      (libsource (lib "eagle-import") (part "R-EU_0603"))
    )
    (comp (ref "R72")
      (value "1M")
      (footprint "eagle-import:0603")
      (libsource (lib "eagle-import") (part "R-EU_0603"))
    )
    (comp (ref "R73")
      (value "10k")
      (footprint "eagle-import:0603")
      (libsource (lib "eagle-import") (part "R-EU_0603"))
    )
    (comp (ref "R74")
      (value "1M")
      (footprint "eagle-import:0603")
      (libsource (lib "eagle-import") (part "R-EU_0603"))
    )
    (comp (ref "R75")
      (value "10k")
      (footprint "eagle-import:0603")
      (libsource (lib "eagle-import") (part "R-EU_0603"))
    )
    (comp (ref "R76")
      (value "10k")
      (footprint "eagle-import:0603")
      (libsource (lib "eagle-import") (part "R-EU_0603"))
    )
    (comp (ref "R77")
      (value "10k")
      (footprint "eagle-import:0603")
      (libsource (lib "eagle-import") (part "R-EU_0603"))
    )
    (comp (ref "R78")
      (value "10k")
      (footprint "eagle-import:0603")
      (libsource (lib "eagle-import") (part "R-EU_0603"))
    )
    (comp (ref "R79")
      (value "10k")
      (footprint "eagle-import:0603")
      (libsource (lib "eagle-import") (part "R-EU_0603"))
    )
    (comp (ref "R80")
      (value "10k")
      (footprint "eagle-import:0603")
      (libsource (lib "eagle-import") (part "R-EU_0603"))
    )
    (comp (ref "R81")
      (value "4k7")
      (footprint "eagle-import:0603")
      (libsource (lib "eagle-import") (part "R-EU_0603"))
    )
    (comp (ref "R82")
      (value "4k7")
      (footprint "eagle-import:0603")
      (libsource (lib "eagle-import") (part "R-EU_0603"))
    )
    (comp (ref "R117")
      (value "10k")
      (footprint "eagle-import:0603")
      (libsource (lib "eagle-import") (part "R-EU_0603"))
    )
    (comp (ref "R118")
      (value "10k")
      (footprint "eagle-import:0603")
      (libsource (lib "eagle-import") (part "R-EU_0603"))
    )
    (comp (ref "R121")
      (value "10k")
      (footprint "eagle-import:0603")
      (libsource (lib "eagle-import") (part "R-EU_0603"))
    )
    (comp (ref "R122")
      (value "10k")
      (footprint "eagle-import:0603")
      (libsource (lib "eagle-import") (part "R-EU_0603"))
    )
    (comp (ref "1K")
      (value "1k")
      (footprint "eagle-import:0603")
      (fields (field (name "MF") "MULTICOMP") (field (name "MPN") "MC0063W06031160K"))
      (libsource (lib "eagle-import") (part "R-EU_0603"))
    )
    (comp (ref "1K1")
      (value "1k")
      (footprint "eagle-import:0603")
      (fields (field (name "MF") "MULTICOMP") (field (name "MPN") "MC0063W06031160K"))
      (libsource (lib "eagle-import") (part "R-EU_0603"))
    )
    (comp (ref "C3")
      (value "560p")
      (footprint "eagle-import:C0603K")
      (libsource (lib "eagle-import") (part "resistor_C-EUC0603K"))
    )
    (comp (ref "C4")
      (value "100p")
      (footprint "eagle-import:C0603K")
      (libsource (lib "eagle-import") (part "resistor_C-EUC0603K"))
    )
    (comp (ref "C5")
      (value "560p")
      (footprint "eagle-import:C0603K")
      (libsource (lib "eagle-import") (part "resistor_C-EUC0603K"))
    )
    (comp (ref "C10")
      (value "4u7")
      (footprint "eagle-import:C0603K")
      (libsource (lib "eagle-import") (part "resistor_C-EUC0603K"))
    )
    (comp (ref "C11")
      (value "560p")
      (footprint "eagle-import:C0603K")
      (libsource (lib "eagle-import") (part "resistor_C-EUC0603K"))
    )
    (comp (ref "C12")
      (value "100p")
      (footprint "eagle-import:C0603K")
      (libsource (lib "eagle-import") (part "resistor_C-EUC0603K"))
    )
    (comp (ref "C14")
      (value "100p")
      (footprint "eagle-import:C0603K")
      (libsource (lib "eagle-import") (part "resistor_C-EUC0603K"))
    )
    (comp (ref "C15")
      (value "560p")
      (footprint "eagle-import:C0603K")
      (libsource (lib "eagle-import") (part "resistor_C-EUC0603K"))
    )
    (comp (ref "C16")
      (value "100p")
      (footprint "eagle-import:C0603K")
      (libsource (lib "eagle-import") (part "resistor_C-EUC0603K"))
    )
    (comp (ref "C20")
      (value "4u7")
      (footprint "eagle-import:C0603K")
      (libsource (lib "eagle-import") (part "resistor_C-EUC0603K"))
    )
    (comp (ref "C21")
      (value "100n")
      (footprint "eagle-import:C0603K")
      (libsource (lib "eagle-import") (part "C-EUC0603K"))
    )
    (comp (ref "C22")
      (value "100n")
      (footprint "eagle-import:C0603K")
      (libsource (lib "eagle-import") (part "C-EUC0603K"))
    )
    (comp (ref "C23")
      (value "100n")
      (footprint "eagle-import:C0603K")
      (libsource (lib "eagle-import") (part "C-EUC0603K"))
    )
    (comp (ref "C24")
      (value "100n")
      (footprint "eagle-import:C0603K")
      (libsource (lib "eagle-import") (part "C-EUC0603K"))
    )
    (comp (ref "C25")
      (value "100n")
      (footprint "eagle-import:C0603K")
      (libsource (lib "eagle-import") (part "C-EUC0603K"))
    )
    (comp (ref "C30")
      (value "100n")
      (footprint "eagle-import:C0603K")
      (libsource (lib "eagle-import") (part "C-EUC0603K"))
    )
    (comp (ref "C40")
      (value "100n")
      (footprint "eagle-import:C0603K")
      (libsource (lib "eagle-import") (part "C-EUC0603K"))
    )
    (comp (ref "C41")
      (value "100n")
      (footprint "eagle-import:C0603K")
      (libsource (lib "eagle-import") (part "C-EUC0603K"))
    )
    (comp (ref "C42")
      (value "100n")
      (footprint "eagle-import:C0603K")
      (libsource (lib "eagle-import") (part "C-EUC0603K"))
    )
    (comp (ref "C43")
      (value "100n")
      (footprint "eagle-import:C0603K")
      (libsource (lib "eagle-import") (part "C-EUC0603K"))
    )
    (comp (ref "C46")
      (value "100n")
      (footprint "eagle-import:C0603K")
      (libsource (lib "eagle-import") (part "C-EUC0603K"))
    )
    (comp (ref "C47")
      (value "100n")
      (footprint "eagle-import:C0603K")
      (libsource (lib "eagle-import") (part "C-EUC0603K"))
    )
    (comp (ref "CLAMP_REF")
      (value "R-TRIMM64W")
      (footprint "eagle-import:RTRIM64W")
      (libsource (lib "eagle-import") (part "R-TRIMM64W"))
    )
    (comp (ref "D1")
      (value "BAT54A")
      (footprint "eagle-import:SOT23")
      (libsource (lib "eagle-import") (part "BAT54A"))
    )
    (comp (ref "D2")
      (value "BAT54A")
      (footprint "eagle-import:SOT23")
      (libsource (lib "eagle-import") (part "BAT54A"))
    )
    (comp (ref "D7")
      (value "BAT54A")
      (footprint "eagle-import:SOT23")
      (libsource (lib "eagle-import") (part "BAT54A"))
    )
    (comp (ref "IC3")
      (value "TL074D")
      (footprint "eagle-import:SO14")
      (libsource (lib "eagle-import") (part "linear@1_TL074D"))
    )
    (comp (ref "IC5")
      (value "TL074D")
      (footprint "eagle-import:SO14")
      (fields (field (name "OC_FARNELL") "unknown"))
      (libsource (lib "eagle-import") (part "TL074D"))
    )
    (comp (ref "IC8")
      (value "TL074D")
      (footprint "eagle-import:SO14")
      (fields (field (name "OC_FARNELL") "unknown"))
      (libsource (lib "eagle-import") (part "TL074D"))
    )
    (comp (ref "JP6")
      (value "M05PTH")
      (footprint "eagle-import:1X05")
      (libsource (lib "eagle-import") (part "M05PTH"))
    )
    (comp (ref "JP7")
      (value "M07")
      (footprint "eagle-import:1X07")
      (libsource (lib "eagle-import") (part "M07"))
    )
    (comp (ref "JP8")
      (value "M05X2PTH")
      (footprint "eagle-import:AVR_ICSP")
      (libsource (lib "eagle-import") (part "M05X2PTH"))
    )
    (comp (ref "JP14")
      (value "M03PTH")
      (footprint "eagle-import:1X03")
      (libsource (lib "eagle-import") (part "M03PTH"))
    )
    (comp (ref "LED_REF")
      (value "R-TRIMM64W")
      (footprint "eagle-import:RTRIM64W")
      (libsource (lib "eagle-import") (part "R-TRIMM64W"))
    )
    (comp (ref "Q9")
      (value "BSS84")
      (footprint "eagle-import:SOT23")
      (libsource (lib "eagle-import") (part "BSS84"))
    )
    (comp (ref "Q10")
      (value "BSS123")
      (footprint "eagle-import:SOT23")
      (libsource (lib "eagle-import") (part "BSS123"))
    )
    (comp (ref "R1")
      (value "1M")
      (footprint "eagle-import:0603")
      (libsource (lib "eagle-import") (part "R-EU_0603"))
    )
    (comp (ref "R5")
      (value "30k")
      (footprint "eagle-import:0603")
      (libsource (lib "eagle-import") (part "R-EU_0603"))
    )
    (comp (ref "R6")
      (value "500")
      (footprint "eagle-import:0603")
      (libsource (lib "eagle-import") (part "R-EU_0603"))
    )
    (comp (ref "R7")
      (value "30k")
      (footprint "eagle-import:0603")
      (libsource (lib "eagle-import") (part "R-EU_0603"))
    )
    (comp (ref "R9")
      (value "10k")
      (footprint "eagle-import:0603")
      (libsource (lib "eagle-import") (part "R-EU_0603"))
    )
    (comp (ref "R10")
      (value "30k")
      (footprint "eagle-import:0603")
      (libsource (lib "eagle-import") (part "R-EU_0603"))
    )
    (comp (ref "R11")
      (value "500")
      (footprint "eagle-import:0603")
      (libsource (lib "eagle-import") (part "R-EU_0603"))
    )
    (comp (ref "R20")
      (value "10k")
      (footprint "eagle-import:0603")
      (libsource (lib "eagle-import") (part "R-EU_0603"))
    )
    (comp (ref "R24")
      (value "2k7")
      (footprint "eagle-import:0603")
      (libsource (lib "eagle-import") (part "R-EU_0603"))
    )
    (comp (ref "R28")
      (value "10k")
      (footprint "eagle-import:0603")
      (libsource (lib "eagle-import") (part "R-EU_0603"))
    )
    (comp (ref "R29")
      (value "10k")
      (footprint "eagle-import:0603")
      (libsource (lib "eagle-import") (part "R-EU_0603"))
    )
    (comp (ref "R30")
      (value "10k")
      (footprint "eagle-import:0603")
      (libsource (lib "eagle-import") (part "R-EU_0603"))
    )
    (comp (ref "R36")
      (value "30k")
      (footprint "eagle-import:0603")
      (libsource (lib "eagle-import") (part "R-EU_0603"))
    )
    (comp (ref "R44")
      (value "560")
      (footprint "eagle-import:0603")
      (libsource (lib "eagle-import") (part "R-EU_0603"))
    )
    (comp (ref "R45")
      (value "30k")
      (footprint "eagle-import:0603")
      (libsource (lib "eagle-import") (part "R-EU_0603"))
    )
    (comp (ref "R47")
      (value "500")
      (footprint "eagle-import:0603")
      (libsource (lib "eagle-import") (part "R-EU_0603"))
    )
    (comp (ref "R48")
      (value "10k")
      (footprint "eagle-import:0603")
      (libsource (lib "eagle-import") (part "R-EU_0603"))
    )
    (comp (ref "R49")
      (value "30k")
      (footprint "eagle-import:0603")
      (libsource (lib "eagle-import") (part "R-EU_0603"))
    )
    (comp (ref "R50")
      (value "1M")
      (footprint "eagle-import:0603")
      (libsource (lib "eagle-import") (part "R-EU_0603"))
    )
    (comp (ref "R51")
      (value "560")
      (footprint "eagle-import:0603")
      (libsource (lib "eagle-import") (part "R-EU_0603"))
    )
    (comp (ref "R54")
      (value "30k")
      (footprint "eagle-import:0603")
      (libsource (lib "eagle-import") (part "R-EU_0603"))
    )
    (comp (ref "R56")
      (value "500")
      (footprint "eagle-import:0603")
      (libsource (lib "eagle-import") (part "R-EU_0603"))
    )
    (comp (ref "R57")
      (value "2k7")
      (footprint "eagle-import:0603")
      (libsource (lib "eagle-import") (part "R-EU_0603"))
    )
    (comp (ref "R62")
      (value "10k")
      (footprint "eagle-import:0603")
      (libsource (lib "eagle-import") (part "R-EU_0603"))
    )
    (comp (ref "R63")
      (value "10k")
      (footprint "eagle-import:0603")
      (libsource (lib "eagle-import") (part "R-EU_0603"))
    )
    (comp (ref "R64")
      (value "30k")
      (footprint "eagle-import:0603")
      (libsource (lib "eagle-import") (part "R-EU_0603"))
    )
    (comp (ref "R66")
      (value "10k")
      (footprint "eagle-import:0603")
      (libsource (lib "eagle-import") (part "R-EU_0603"))
    )
    (comp (ref "R67")
      (value "10k")
      (footprint "eagle-import:0603")
      (libsource (lib "eagle-import") (part "R-EU_0603"))
    )
    (comp (ref "R68")
      (value "10k")
      (footprint "eagle-import:0603")
      (libsource (lib "eagle-import") (part "R-EU_0603"))
    )
    (comp (ref "R69")
      (value "560")
      (footprint "eagle-import:0603")
      (libsource (lib "eagle-import") (part "R-EU_0603"))
    )
    (comp (ref "R70")
      (value "560")
      (footprint "eagle-import:0603")
      (libsource (lib "eagle-import") (part "R-EU_0603"))
    )
    (comp (ref "R71")
      (value "10k")
      (footprint "eagle-import:0603")
      (libsource (lib "eagle-import") (part "R-EU_0603"))
    )
    (comp (ref "R94")
      (value "6k")
      (footprint "eagle-import:0603")
      (libsource (lib "eagle-import") (part "R-EU_0603"))
    )
    (comp (ref "R104")
      (value "10k")
      (footprint "eagle-import:0603")
      (libsource (lib "eagle-import") (part "R-EU_0603"))
    )
    (comp (ref "R105")
      (value "2k7")
      (footprint "eagle-import:0603")
      (libsource (lib "eagle-import") (part "R-EU_0603"))
    )
    (comp (ref "R109")
      (value "10k")
      (footprint "eagle-import:0603")
      (libsource (lib "eagle-import") (part "R-EU_0603"))
    )
    (comp (ref "R110")
      (value "6k")
      (footprint "eagle-import:0603")
      (libsource (lib "eagle-import") (part "R-EU_0603"))
    )
    (comp (ref "R111")
      (value "2k7")
      (footprint "eagle-import:0603")
      (libsource (lib "eagle-import") (part "R-EU_0603"))
    )
    (comp (ref "R112")
      (value "10k")
      (footprint "eagle-import:0603")
      (libsource (lib "eagle-import") (part "R-EU_0603"))
    )
    (comp (ref "R113")
      (value "10k")
      (footprint "eagle-import:0603")
      (libsource (lib "eagle-import") (part "R-EU_0603"))
    )
    (comp (ref "R114")
      (value "10k")
      (footprint "eagle-import:0603")
      (libsource (lib "eagle-import") (part "R-EU_0603"))
    )
    (comp (ref "R119")
      (value "10k")
      (footprint "eagle-import:0603")
      (libsource (lib "eagle-import") (part "R-EU_0603"))
    )
    (comp (ref "R120")
      (value "10k")
      (footprint "eagle-import:0603")
      (libsource (lib "eagle-import") (part "R-EU_0603"))
    )
  )
  (nets
    (net (code "1") (name "+12V") (class "Default")
      (node (ref "C21") (pin "1") (pinfunction "1_1") (pintype "passive"))
      (node (ref "C23") (pin "1") (pinfunction "1_1") (pintype "passive"))
      (node (ref "C24") (pin "1") (pinfunction "1_1") (pintype "passive"))
      (node (ref "C26") (pin "1") (pinfunction "1_1") (pintype "passive"))
      (node (ref "C28") (pin "1") (pinfunction "1_1") (pintype "passive"))
      (node (ref "C32") (pin "1") (pinfunction "1_1") (pintype "passive"))
      (node (ref "C34") (pin "1") (pinfunction "1_1") (pintype "passive"))
      (node (ref "C36") (pin "1") (pinfunction "1_1") (pintype "passive"))
      (node (ref "C40") (pin "1") (pinfunction "1_1") (pintype "passive"))
      (node (ref "C42") (pin "1") (pinfunction "1_1") (pintype "passive"))
      (node (ref "C44") (pin "1") (pinfunction "1_1") (pintype "passive"))
      (node (ref "C46") (pin "1") (pinfunction "1_1") (pintype "passive"))
      (node (ref "IC1") (pin "4") (pinfunction "V+_4") (pintype "power_in"))
      (node (ref "IC10") (pin "4") (pinfunction "V+_4") (pintype "power_in"))
      (node (ref "IC12") (pin "4") (pinfunction "V+_4") (pintype "power_in"))
      (node (ref "IC14") (pin "4") (pinfunction "V+_4") (pintype "power_in"))
      (node (ref "IC2") (pin "16") (pinfunction "V+_16") (pintype "power_in"))
      (node (ref "IC3") (pin "4") (pinfunction "V+_4") (pintype "power_in"))
      (node (ref "IC4") (pin "8") (pinfunction "V+_8") (pintype "power_in"))
      (node (ref "IC5") (pin "4") (pinfunction "V+_4") (pintype "power_in"))
      (node (ref "IC6") (pin "16") (pinfunction "V+_16") (pintype "power_in"))
      (node (ref "IC7") (pin "4") (pinfunction "V+_4") (pintype "power_in"))
      (node (ref "IC8") (pin "4") (pinfunction "V+_4") (pintype "power_in"))
      (node (ref "IC9") (pin "4") (pinfunction "V+_4") (pintype "power_in"))
      (node (ref "Q9") (pin "2") (pinfunction "S_2") (pintype "passive"))
      (node (ref "R110") (pin "2") (pinfunction "2_2") (pintype "passive"))
      (node (ref "R117") (pin "1") (pinfunction "1_1") (pintype "passive"))
      (node (ref "R121") (pin "1") (pinfunction "1_1") (pintype "passive"))
      (node (ref "R93") (pin "2") (pinfunction "2_2") (pintype "passive"))
      (node (ref "R94") (pin "2") (pinfunction "2_2") (pintype "passive"))
    )
    (net (code "2") (name "-12V") (class "Default")
      (node (ref "C22") (pin "2") (pinfunction "2_2") (pintype "passive"))
      (node (ref "C25") (pin "1") (pinfunction "1_1") (pintype "passive"))
      (node (ref "C27") (pin "1") (pinfunction "1_1") (pintype "passive"))
      (node (ref "C29") (pin "1") (pinfunction "1_1") (pintype "passive"))
      (node (ref "C30") (pin "1") (pinfunction "1_1") (pintype "passive"))
      (node (ref "C33") (pin "1") (pinfunction "1_1") (pintype "passive"))
      (node (ref "C35") (pin "1") (pinfunction "1_1") (pintype "passive"))
      (node (ref "C37") (pin "1") (pinfunction "1_1") (pintype "passive"))
      (node (ref "C41") (pin "1") (pinfunction "1_1") (pintype "passive"))
      (node (ref "C43") (pin "2") (pinfunction "2_2") (pintype "passive"))
      (node (ref "C45") (pin "1") (pinfunction "1_1") (pintype "passive"))
      (node (ref "C47") (pin "1") (pinfunction "1_1") (pintype "passive"))
      (node (ref "D7") (pin "3") (pinfunction "AA_3") (pintype "passive"))
      (node (ref "IC1") (pin "11") (pinfunction "V-_11") (pintype "power_in"))
      (node (ref "IC10") (pin "11") (pinfunction "V-_11") (pintype "power_in"))
      (node (ref "IC12") (pin "11") (pinfunction "V-_11") (pintype "power_in"))
      (node (ref "IC14") (pin "11") (pinfunction "V-_11") (pintype "power_in"))
      (node (ref "IC2") (pin "9") (pinfunction "V-_9") (pintype "power_in"))
      (node (ref "IC3") (pin "11") (pinfunction "V-_11") (pintype "power_in"))
      (node (ref "IC4") (pin "4") (pinfunction "V-_4") (pintype "power_in"))
      (node (ref "IC5") (pin "11") (pinfunction "V-_11") (pintype "power_in"))
      (node (ref "IC6") (pin "9") (pinfunction "V-_9") (pintype "power_in"))
      (node (ref "IC7") (pin "11") (pinfunction "V-_11") (pintype "power_in"))
      (node (ref "IC8") (pin "11") (pinfunction "V-_11") (pintype "power_in"))
      (node (ref "IC9") (pin "11") (pinfunction "V-_11") (pintype "power_in"))
      (node (ref "Q10") (pin "2") (pinfunction "S_2") (pintype "passive"))
      (node (ref "R118") (pin "2") (pinfunction "2_2") (pintype "passive"))
      (node (ref "R122") (pin "2") (pinfunction "2_2") (pintype "passive"))
      (node (ref "R63") (pin "1") (pinfunction "1_1") (pintype "passive"))
    )
    (net (code "3") (name "CLAMP_REF") (class "Default")
      (node (ref "D1") (pin "3") (pinfunction "AA_3") (pintype "passive"))
      (node (ref "D2") (pin "3") (pinfunction "AA_3") (pintype "passive"))
      (node (ref "IC4") (pin "1") (pinfunction "OUT_1") (pintype "output"))
      (node (ref "IC4") (pin "2") (pinfunction "-IN_2") (pintype "input"))
    )
    (net (code "4") (name "CV_EXPA") (class "Default")
      (node (ref "CV_EXP_A") (pin "P$3") (pinfunction "3_P$3") (pintype "passive"))
      (node (ref "CV_LIN_A") (pin "P$2") (pinfunction "4_P$2") (pintype "passive"))
      (node (ref "IC1") (pin "5") (pinfunction "+IN_5") (pintype "input"))
      (node (ref "JP11") (pin "4") (pinfunction "4_4") (pintype "passive"))
      (node (ref "JP12") (pin "4") (pinfunction "4_4") (pintype "passive"))
      (node (ref "R65") (pin "1") (pinfunction "1_1") (pintype "passive"))
    )
    (net (code "5") (name "CV_EXPB") (class "Default")
      (node (ref "CV_EXP_B") (pin "P$3") (pinfunction "3_P$3") (pintype "passive"))
      (node (ref "CV_LIN_B") (pin "P$2") (pinfunction "4_P$2") (pintype "passive"))
      (node (ref "IC9") (pin "5") (pinfunction "+IN_5") (pintype "input"))
      (node (ref "JP11") (pin "2") (pinfunction "2_2") (pintype "passive"))
      (node (ref "JP12") (pin "2") (pinfunction "2_2") (pintype "passive"))
      (node (ref "R74") (pin "1") (pinfunction "1_1") (pintype "passive"))
    )
    (net (code "6") (name "CV_LINA") (class "Default")
      (node (ref "CV_EXP_A") (pin "P$2") (pinfunction "4_P$2") (pintype "passive"))
      (node (ref "CV_LIN_A") (pin "P$3") (pinfunction "3_P$3") (pintype "passive"))
      (node (ref "IC1") (pin "3") (pinfunction "+IN_3") (pintype "input"))
      (node (ref "JP11") (pin "5") (pinfunction "5_5") (pintype "passive"))
      (node (ref "JP12") (pin "5") (pinfunction "5_5") (pintype "passive"))
      (node (ref "R52") (pin "1") (pinfunction "1_1") (pintype "passive"))
    )
    (net (code "7") (name "CV_LINB") (class "Default")
      (node (ref "CV_EXP_B") (pin "P$2") (pinfunction "4_P$2") (pintype "passive"))
      (node (ref "CV_LIN_B") (pin "P$3") (pinfunction "3_P$3") (pintype "passive"))
      (node (ref "IC9") (pin "3") (pinfunction "+IN_3") (pintype "input"))
      (node (ref "JP11") (pin "1") (pinfunction "1_1") (pintype "passive"))
      (node (ref "JP12") (pin "1") (pinfunction "1_1") (pintype "passive"))
      (node (ref "R72") (pin "1") (pinfunction "1_1") (pintype "passive"))
    )
    (net (code "8") (name "CV_SUM+_A") (class "Default")
      (node (ref "IC14") (pin "7") (pinfunction "OUT_7") (pintype "output"))
      (node (ref "R38") (pin "1") (pinfunction "1_1") (pintype "passive"))
      (node (ref "R51") (pin "2") (pinfunction "2_2") (pintype "passive"))
    )
    (net (code "9") (name "CV_SUM+_B") (class "Default")
      (node (ref "IC12") (pin "7") (pinfunction "OUT_7") (pintype "output"))
      (node (ref "R69") (pin "2") (pinfunction "2_2") (pintype "passive"))
      (node (ref "R99") (pin "1") (pinfunction "1_1") (pintype "passive"))
    )
    (net (code "10") (name "CV_SUM-_A") (class "Default")
      (node (ref "IC14") (pin "8") (pinfunction "OUT_8") (pintype "output"))
      (node (ref "R19") (pin "1") (pinfunction "1_1") (pintype "passive"))
      (node (ref "R44") (pin "2") (pinfunction "2_2") (pintype "passive"))
    )
    (net (code "11") (name "CV_SUM-_B") (class "Default")
      (node (ref "IC12") (pin "8") (pinfunction "OUT_8") (pintype "output"))
      (node (ref "R108") (pin "1") (pinfunction "1_1") (pintype "passive"))
      (node (ref "R70") (pin "2") (pinfunction "2_2") (pintype "passive"))
    )
    (net (code "12") (name "EXP_NEG_A") (class "Default")
      (node (ref "D5") (pin "2") (pinfunction "C2_2") (pintype "passive"))
      (node (ref "R40") (pin "2") (pinfunction "2_2") (pintype "passive"))
    )
    (net (code "13") (name "EXP_NEG_B") (class "Default")
      (node (ref "D6") (pin "2") (pinfunction "C2_2") (pintype "passive"))
      (node (ref "R107") (pin "2") (pinfunction "2_2") (pintype "passive"))
    )
    (net (code "14") (name "EXP_POS_A") (class "Default")
      (node (ref "D5") (pin "1") (pinfunction "A1_1") (pintype "passive"))
      (node (ref "R42") (pin "2") (pinfunction "2_2") (pintype "passive"))
    )
    (net (code "15") (name "EXP_POS_B") (class "Default")
      (node (ref "D6") (pin "1") (pinfunction "A1_1") (pintype "passive"))
      (node (ref "R101") (pin "2") (pinfunction "2_2") (pintype "passive"))
    )
    (net (code "16") (name "GND") (class "Default")
      (node (ref "140K") (pin "1") (pinfunction "1_1") (pintype "passive"))
      (node (ref "140K1") (pin "1") (pinfunction "1_1") (pintype "passive"))
      (node (ref "140K2") (pin "1") (pinfunction "1_1") (pintype "passive"))
      (node (ref "140K3") (pin "1") (pinfunction "1_1") (pintype "passive"))
      (node (ref "C1") (pin "2") (pinfunction "2_2") (pintype "passive"))
      (node (ref "C10") (pin "2") (pinfunction "2_2") (pintype "passive"))
      (node (ref "C11") (pin "2") (pinfunction "2_2") (pintype "passive"))
      (node (ref "C15") (pin "2") (pinfunction "2_2") (pintype "passive"))
      (node (ref "C17") (pin "2") (pinfunction "2_2") (pintype "passive"))
      (node (ref "C19") (pin "2") (pinfunction "2_2") (pintype "passive"))
      (node (ref "C2") (pin "2") (pinfunction "2_2") (pintype "passive"))
      (node (ref "C20") (pin "2") (pinfunction "2_2") (pintype "passive"))
      (node (ref "C21") (pin "2") (pinfunction "2_2") (pintype "passive"))
      (node (ref "C22") (pin "1") (pinfunction "1_1") (pintype "passive"))
      (node (ref "C23") (pin "2") (pinfunction "2_2") (pintype "passive"))
      (node (ref "C24") (pin "2") (pinfunction "2_2") (pintype "passive"))
      (node (ref "C25") (pin "2") (pinfunction "2_2") (pintype "passive"))
      (node (ref "C26") (pin "2") (pinfunction "2_2") (pintype "passive"))
      (node (ref "C27") (pin "2") (pinfunction "2_2") (pintype "passive"))
      (node (ref "C28") (pin "2") (pinfunction "2_2") (pintype "passive"))
      (node (ref "C29") (pin "2") (pinfunction "2_2") (pintype "passive"))
      (node (ref "C3") (pin "2") (pinfunction "2_2") (pintype "passive"))
      (node (ref "C30") (pin "2") (pinfunction "2_2") (pintype "passive"))
      (node (ref "C32") (pin "2") (pinfunction "2_2") (pintype "passive"))
      (node (ref "C33") (pin "2") (pinfunction "2_2") (pintype "passive"))
      (node (ref "C34") (pin "2") (pinfunction "2_2") (pintype "passive"))
      (node (ref "C35") (pin "2") (pinfunction "2_2") (pintype "passive"))
      (node (ref "C36") (pin "2") (pinfunction "2_2") (pintype "passive"))
      (node (ref "C37") (pin "2") (pinfunction "2_2") (pintype "passive"))
      (node (ref "C40") (pin "2") (pinfunction "2_2") (pintype "passive"))
      (node (ref "C41") (pin "2") (pinfunction "2_2") (pintype "passive"))
      (node (ref "C42") (pin "2") (pinfunction "2_2") (pintype "passive"))
      (node (ref "C43") (pin "1") (pinfunction "1_1") (pintype "passive"))
      (node (ref "C44") (pin "2") (pinfunction "2_2") (pintype "passive"))
      (node (ref "C45") (pin "2") (pinfunction "2_2") (pintype "passive"))
      (node (ref "C46") (pin "2") (pinfunction "2_2") (pintype "passive"))
      (node (ref "C47") (pin "2") (pinfunction "2_2") (pintype "passive"))
      (node (ref "C5") (pin "2") (pinfunction "2_2") (pintype "passive"))
      (node (ref "C7") (pin "2") (pinfunction "2_2") (pintype "passive"))
      (node (ref "C9") (pin "2") (pinfunction "2_2") (pintype "passive"))
      (node (ref "CV_EXP_A") (pin "P$1") (pinfunction "5_P$1") (pintype "passive"))
      (node (ref "CV_EXP_B") (pin "P$1") (pinfunction "5_P$1") (pintype "passive"))
      (node (ref "CV_LIN_A") (pin "P$1") (pinfunction "5_P$1") (pintype "passive"))
      (node (ref "CV_LIN_B") (pin "P$1") (pinfunction "5_P$1") (pintype "passive"))
      (node (ref "D7") (pin "1") (pinfunction "K1_1") (pintype "passive"))
      (node (ref "D7") (pin "2") (pinfunction "K2_2") (pintype "passive"))
      (node (ref "IC10") (pin "5") (pinfunction "+IN_5") (pintype "input"))
      (node (ref "IC12") (pin "12") (pinfunction "+IN_12") (pintype "input"))
      (node (ref "IC12") (pin "3") (pinfunction "+IN_3") (pintype "input"))
      (node (ref "IC13") (pin "2") (pinfunction "A_2") (pintype "passive"))
      (node (ref "IC14") (pin "12") (pinfunction "+IN_12") (pintype "input"))
      (node (ref "IC14") (pin "3") (pinfunction "+IN_3") (pintype "input"))
      (node (ref "IC2") (pin "8") (pinfunction "GND_8") (pintype "power_in"))
      (node (ref "IC5") (pin "10") (pinfunction "+IN_10") (pintype "input"))
      (node (ref "IC5") (pin "5") (pinfunction "+IN_5") (pintype "input"))
      (node (ref "IC6") (pin "8") (pinfunction "GND_8") (pintype "power_in"))
      (node (ref "IC7") (pin "5") (pinfunction "+IN_5") (pintype "input"))
      (node (ref "IC8") (pin "10") (pinfunction "+IN_10") (pintype "input"))
      (node (ref "IC8") (pin "5") (pinfunction "+IN_5") (pintype "input"))
      (node (ref "IN_A") (pin "P$1") (pinfunction "5_P$1") (pintype "passive"))
      (node (ref "IN_A") (pin "P$2") (pinfunction "4_P$2") (pintype "passive"))
      (node (ref "IN_B") (pin "P$1") (pinfunction "5_P$1") (pintype "passive"))
      (node (ref "IN_B") (pin "P$2") (pinfunction "4_P$2") (pintype "passive"))
      (node (ref "J2") (pin "4") (pinfunction "4_4") (pintype "passive"))
      (node (ref "JP1") (pin "3") (pinfunction "3_3") (pintype "passive"))
      (node (ref "JP11") (pin "3") (pinfunction "3_3") (pintype "passive"))
      (node (ref "JP12") (pin "3") (pinfunction "3_3") (pintype "passive"))
      (node (ref "JP13") (pin "2") (pinfunction "2_2") (pintype "passive"))
      (node (ref "JP14") (pin "2") (pinfunction "2_2") (pintype "passive"))
      (node (ref "JP2") (pin "5") (pinfunction "5_5") (pintype "passive"))
      (node (ref "JP3") (pin "5") (pinfunction "5_5") (pintype "passive"))
      (node (ref "JP4") (pin "4") (pinfunction "4_4") (pintype "passive"))
      (node (ref "JP5") (pin "4") (pinfunction "4_4") (pintype "passive"))
      (node (ref "JP6") (pin "3") (pinfunction "3_3") (pintype "passive"))
      (node (ref "JP7") (pin "4") (pinfunction "4_4") (pintype "passive"))
      (node (ref "JP8") (pin "3") (pinfunction "3_3") (pintype "passive"))
      (node (ref "JP8") (pin "4") (pinfunction "4_4") (pintype "passive"))
      (node (ref "JP8") (pin "5") (pinfunction "5_5") (pintype "passive"))
      (node (ref "JP8") (pin "6") (pinfunction "6_6") (pintype "passive"))
      (node (ref "JP8") (pin "7") (pinfunction "7_7") (pintype "passive"))
      (node (ref "JP8") (pin "8") (pinfunction "8_8") (pintype "passive"))
      (node (ref "LD1") (pin "C") (pinfunction "C_C") (pintype "passive"))
      (node (ref "LD2") (pin "C") (pinfunction "C_C") (pintype "passive"))
      (node (ref "LED_REF") (pin "1") (pinfunction "A_1") (pintype "passive"))
      (node (ref "OFFSET_LINA") (pin "1") (pinfunction "A_1") (pintype "passive"))
      (node (ref "OFFSET_REF") (pin "1") (pinfunction "A_1") (pintype "passive"))
      (node (ref "OUT_A") (pin "P$1") (pinfunction "5_P$1") (pintype "passive"))
      (node (ref "OUT_A") (pin "P$2") (pinfunction "4_P$2") (pintype "passive"))
      (node (ref "OUT_B") (pin "P$1") (pinfunction "5_P$1") (pintype "passive"))
      (node (ref "OUT_B") (pin "P$2") (pinfunction "4_P$2") (pintype "passive"))
      (node (ref "POT_EXPA") (pin "2") (pinfunction "2_2") (pintype "bidirectional"))
      (node (ref "POT_EXPB") (pin "2") (pinfunction "2_2") (pintype "bidirectional"))
      (node (ref "POT_LINA") (pin "2") (pinfunction "2_2") (pintype "bidirectional"))
      (node (ref "POT_LINB") (pin "2") (pinfunction "2_2") (pintype "bidirectional"))
      (node (ref "Q10") (pin "1") (pinfunction "G_1") (pintype "passive"))
      (node (ref "Q9") (pin "1") (pinfunction "G_1") (pintype "passive"))
      (node (ref "R1") (pin "2") (pinfunction "2_2") (pintype "passive"))
      (node (ref "R103") (pin "2") (pinfunction "2_2") (pintype "passive"))
      (node (ref "R119") (pin "2") (pinfunction "2_2") (pintype "passive"))
      (node (ref "R120") (pin "2") (pinfunction "2_2") (pintype "passive"))
      (node (ref "R27") (pin "2") (pinfunction "2_2") (pintype "passive"))
      (node (ref "R30") (pin "2") (pinfunction "2_2") (pintype "passive"))
      (node (ref "R43") (pin "2") (pinfunction "2_2") (pintype "passive"))
      (node (ref "R50") (pin "2") (pinfunction "2_2") (pintype "passive"))
      (node (ref "R52") (pin "2") (pinfunction "2_2") (pintype "passive"))
      (node (ref "R65") (pin "2") (pinfunction "2_2") (pintype "passive"))
      (node (ref "R71") (pin "2") (pinfunction "2_2") (pintype "passive"))
      (node (ref "R72") (pin "2") (pinfunction "2_2") (pintype "passive"))
      (node (ref "R74") (pin "2") (pinfunction "2_2") (pintype "passive"))
      (node (ref "R96") (pin "2") (pinfunction "2_2") (pintype "passive"))
    )
    (net (code "17") (name "IN1") (class "Default")
      (node (ref "IC8") (pin "1") (pinfunction "OUT_1") (pintype "output"))
      (node (ref "IC8") (pin "2") (pinfunction "-IN_2") (pintype "input"))
      (node (ref "R45") (pin "1") (pinfunction "1_1") (pintype "passive"))
      (node (ref "R54") (pin "1") (pinfunction "1_1") (pintype "passive"))
    )
    (net (code "18") (name "IN2") (class "Default")
      (node (ref "IC5") (pin "1") (pinfunction "OUT_1") (pintype "output"))
      (node (ref "IC5") (pin "2") (pinfunction "-IN_2") (pintype "input"))
      (node (ref "R5") (pin "1") (pinfunction "1_1") (pintype "passive"))
      (node (ref "R7") (pin "1") (pinfunction "1_1") (pintype "passive"))
    )
    (net (code "19") (name "INV_A") (class "Default")
      (node (ref "IC5") (pin "12") (pinfunction "+IN_12") (pintype "input"))
      (node (ref "JP1") (pin "2") (pinfunction "2_2") (pintype "passive"))
      (node (ref "JP6") (pin "2") (pinfunction "2_2") (pintype "passive"))
      (node (ref "R20") (pin "2") (pinfunction "2_2") (pintype "passive"))
      (node (ref "R30") (pin "1") (pinfunction "1_1") (pintype "passive"))
      (node (ref "S1") (pin "2") (pinfunction "P_2") (pintype "passive"))
    )
    (net (code "20") (name "INV_B") (class "Default")
      (node (ref "IC8") (pin "12") (pinfunction "+IN_12") (pintype "input"))
      (node (ref "JP1") (pin "5") (pinfunction "5_5") (pintype "passive"))
      (node (ref "JP6") (pin "5") (pinfunction "5_5") (pintype "passive"))
      (node (ref "R66") (pin "2") (pinfunction "2_2") (pintype "passive"))
      (node (ref "R71") (pin "1") (pinfunction "1_1") (pintype "passive"))
      (node (ref "S2") (pin "2") (pinfunction "P_2") (pintype "passive"))
    )
    (net (code "21") (name "IN_A") (class "Default")
      (node (ref "IC5") (pin "3") (pinfunction "+IN_3") (pintype "input"))
      (node (ref "IN_A") (pin "P$3") (pinfunction "3_P$3") (pintype "passive"))
      (node (ref "JP13") (pin "3") (pinfunction "3_3") (pintype "passive"))
      (node (ref "JP14") (pin "3") (pinfunction "3_3") (pintype "passive"))
      (node (ref "R1") (pin "1") (pinfunction "1_1") (pintype "passive"))
    )
    (net (code "22") (name "IN_B") (class "Default")
      (node (ref "IC8") (pin "3") (pinfunction "+IN_3") (pintype "input"))
      (node (ref "IN_B") (pin "P$3") (pinfunction "3_P$3") (pintype "passive"))
      (node (ref "JP13") (pin "1") (pinfunction "1_1") (pintype "passive"))
      (node (ref "JP14") (pin "1") (pinfunction "1_1") (pintype "passive"))
      (node (ref "R50") (pin "1") (pinfunction "1_1") (pintype "passive"))
    )
    (net (code "23") (name "LED_A+") (class "Default")
      (node (ref "J2") (pin "3") (pinfunction "3_3") (pintype "passive"))
      (node (ref "JP7") (pin "3") (pinfunction "3_3") (pintype "passive"))
      (node (ref "LD1") (pin "AR") (pinfunction "AR_AR") (pintype "passive"))
      (node (ref "R24") (pin "1") (pinfunction "1_1") (pintype "passive"))
    )
    (net (code "24") (name "LED_A-") (class "Default")
      (node (ref "J2") (pin "2") (pinfunction "2_2") (pintype "passive"))
      (node (ref "JP7") (pin "2") (pinfunction "2_2") (pintype "passive"))
      (node (ref "LD1") (pin "AX") (pinfunction "AY_AX") (pintype "passive"))
      (node (ref "R57") (pin "1") (pinfunction "1_1") (pintype "passive"))
    )
    (net (code "25") (name "LED_B+") (class "Default")
      (node (ref "J2") (pin "7") (pinfunction "7_7") (pintype "passive"))
      (node (ref "JP7") (pin "7") (pinfunction "7_7") (pintype "passive"))
      (node (ref "LD2") (pin "AR") (pinfunction "AR_AR") (pintype "passive"))
      (node (ref "R105") (pin "2") (pinfunction "2_2") (pintype "passive"))
    )
    (net (code "26") (name "LED_B-") (class "Default")
      (node (ref "J2") (pin "6") (pinfunction "6_6") (pintype "passive"))
      (node (ref "JP7") (pin "6") (pinfunction "6_6") (pintype "passive"))
      (node (ref "LD2") (pin "AX") (pinfunction "AY_AX") (pintype "passive"))
      (node (ref "R111") (pin "2") (pinfunction "2_2") (pintype "passive"))
    )
    (net (code "27") (name "LED_VREF") (class "Default")
      (node (ref "IC12") (pin "14") (pinfunction "OUT_14") (pintype "output"))
      (node (ref "IC3") (pin "10") (pinfunction "+IN_10") (pintype "input"))
      (node (ref "IC3") (pin "12") (pinfunction "+IN_12") (pintype "input"))
      (node (ref "IC3") (pin "3") (pinfunction "+IN_3") (pintype "input"))
      (node (ref "IC3") (pin "5") (pinfunction "+IN_5") (pintype "input"))
      (node (ref "R114") (pin "1") (pinfunction "1_1") (pintype "passive"))
    )
    (net (code "28") (name "LIN+_OUT_A") (class "Default")
      (node (ref "C6") (pin "1") (pinfunction "1_1") (pintype "passive"))
      (node (ref "IC2") (pin "14") (pinfunction "CTRL_14") (pintype "input"))
      (node (ref "IC7") (pin "14") (pinfunction "OUT_14") (pintype "output"))
      (node (ref "R26") (pin "2") (pinfunction "2_2") (pintype "passive"))
    )
    (net (code "29") (name "LIN+_OUT_B") (class "Default")
      (node (ref "C18") (pin "1") (pinfunction "1_1") (pintype "passive"))
      (node (ref "IC10") (pin "14") (pinfunction "OUT_14") (pintype "output"))
      (node (ref "IC6") (pin "3") (pinfunction "CTRL_3") (pintype "input"))
      (node (ref "R95") (pin "2") (pinfunction "2_2") (pintype "passive"))
    )
    (net (code "30") (name "LIN-_OUT_A") (class "Default")
      (node (ref "C13") (pin "1") (pinfunction "1_1") (pintype "passive"))
      (node (ref "IC2") (pin "3") (pinfunction "CTRL_3") (pintype "input"))
      (node (ref "IC7") (pin "8") (pinfunction "OUT_8") (pintype "output"))
      (node (ref "R41") (pin "2") (pinfunction "2_2") (pintype "passive"))
    )
    (net (code "31") (name "LIN-_OUT_B") (class "Default")
      (node (ref "C8") (pin "1") (pinfunction "1_1") (pintype "passive"))
      (node (ref "IC10") (pin "8") (pinfunction "OUT_8") (pintype "output"))
      (node (ref "IC6") (pin "14") (pinfunction "CTRL_14") (pintype "input"))
      (node (ref "R98") (pin "2") (pinfunction "2_2") (pintype "passive"))
    )
    (net (code "32") (name "LINBIASA_1") (class "Default")
      (node (ref "JP4") (pin "3") (pinfunction "3_3") (pintype "passive"))
      (node (ref "JP5") (pin "3") (pinfunction "3_3") (pintype "passive"))
      (node (ref "POT_LINBIASA") (pin "1") (pinfunction "1_1") (pintype "bidirectional"))
      (node (ref "R121") (pin "2") (pinfunction "2_2") (pintype "passive"))
    )
    (net (code "33") (name "LINBIASA_2") (class "Default")
      (node (ref "JP4") (pin "2") (pinfunction "2_2") (pintype "passive"))
      (node (ref "JP5") (pin "2") (pinfunction "2_2") (pintype "passive"))
      (node (ref "POT_LINBIASA") (pin "2") (pinfunction "2_2") (pintype "bidirectional"))
      (node (ref "R53") (pin "1") (pinfunction "1_1") (pintype "passive"))
    )
    (net (code "34") (name "LINBIASA_3") (class "Default")
      (node (ref "JP4") (pin "1") (pinfunction "1_1") (pintype "passive"))
      (node (ref "JP5") (pin "1") (pinfunction "1_1") (pintype "passive"))
      (node (ref "POT_LINBIASA") (pin "3") (pinfunction "3_3") (pintype "bidirectional"))
      (node (ref "R122") (pin "1") (pinfunction "1_1") (pintype "passive"))
    )
    (net (code "35") (name "LINBIASB_1") (class "Default")
      (node (ref "JP4") (pin "7") (pinfunction "7_7") (pintype "passive"))
      (node (ref "JP5") (pin "7") (pinfunction "7_7") (pintype "passive"))
      (node (ref "POT_LINBIASB") (pin "1") (pinfunction "1_1") (pintype "bidirectional"))
      (node (ref "R117") (pin "2") (pinfunction "2_2") (pintype "passive"))
    )
    (net (code "36") (name "LINBIASB_2") (class "Default")
      (node (ref "JP4") (pin "6") (pinfunction "6_6") (pintype "passive"))
      (node (ref "JP5") (pin "6") (pinfunction "6_6") (pintype "passive"))
      (node (ref "POT_LINBIASB") (pin "2") (pinfunction "2_2") (pintype "bidirectional"))
      (node (ref "R73") (pin "1") (pinfunction "1_1") (pintype "passive"))
    )
    (net (code "37") (name "LINBIASB_3") (class "Default")
      (node (ref "JP4") (pin "5") (pinfunction "5_5") (pintype "passive"))
      (node (ref "JP5") (pin "5") (pinfunction "5_5") (pintype "passive"))
      (node (ref "POT_LINBIASB") (pin "3") (pinfunction "3_3") (pintype "bidirectional"))
      (node (ref "R118") (pin "1") (pinfunction "1_1") (pintype "passive"))
    )
    (net (code "38") (name "LIN_NEG_A") (class "Default")
      (node (ref "D3") (pin "2") (pinfunction "C2_2") (pintype "passive"))
      (node (ref "R32") (pin "1") (pinfunction "1_1") (pintype "passive"))
    )
    (net (code "39") (name "LIN_NEG_B") (class "Default")
      (node (ref "D4") (pin "2") (pinfunction "C2_2") (pintype "passive"))
      (node (ref "R16") (pin "1") (pinfunction "1_1") (pintype "passive"))
    )
    (net (code "40") (name "LIN_POS_A") (class "Default")
      (node (ref "D3") (pin "1") (pinfunction "A1_1") (pintype "passive"))
      (node (ref "R55") (pin "1") (pinfunction "1_1") (pintype "passive"))
    )
    (net (code "41") (name "LIN_POS_B") (class "Default")
      (node (ref "D4") (pin "1") (pinfunction "A1_1") (pintype "passive"))
      (node (ref "R87") (pin "1") (pinfunction "1_1") (pintype "passive"))
    )
    (net (code "42") (name "Net-(140K-Pad2)") (class "Default")
      (node (ref "140K") (pin "2") (pinfunction "2_2") (pintype "passive"))
      (node (ref "R34") (pin "1") (pinfunction "1_1") (pintype "passive"))
      (node (ref "R37") (pin "1") (pinfunction "1_1") (pintype "passive"))
    )
    (net (code "43") (name "Net-(140K1-Pad2)") (class "Default")
      (node (ref "140K1") (pin "2") (pinfunction "2_2") (pintype "passive"))
      (node (ref "R59") (pin "1") (pinfunction "1_1") (pintype "passive"))
      (node (ref "R61") (pin "1") (pinfunction "1_1") (pintype "passive"))
    )
    (net (code "44") (name "Net-(140K2-Pad2)") (class "Default")
      (node (ref "140K2") (pin "2") (pinfunction "2_2") (pintype "passive"))
      (node (ref "R84") (pin "1") (pinfunction "1_1") (pintype "passive"))
      (node (ref "R86") (pin "1") (pinfunction "1_1") (pintype "passive"))
    )
    (net (code "45") (name "Net-(140K3-Pad2)") (class "Default")
      (node (ref "140K3") (pin "2") (pinfunction "2_2") (pintype "passive"))
      (node (ref "R89") (pin "1") (pinfunction "1_1") (pintype "passive"))
      (node (ref "R91") (pin "1") (pinfunction "1_1") (pintype "passive"))
    )
    (net (code "46") (name "Net-(C2-Pad1)") (class "Default")
      (node (ref "C2") (pin "1") (pinfunction "1_1") (pintype "passive"))
      (node (ref "R35") (pin "1") (pinfunction "1_1") (pintype "passive"))
    )
    (net (code "47") (name "Net-(C3-Pad1)") (class "Default")
      (node (ref "C3") (pin "1") (pinfunction "1_1") (pintype "passive"))
      (node (ref "R6") (pin "1") (pinfunction "1_1") (pintype "passive"))
    )
    (net (code "48") (name "Net-(C5-Pad1)") (class "Default")
      (node (ref "C5") (pin "1") (pinfunction "1_1") (pintype "passive"))
      (node (ref "R11") (pin "1") (pinfunction "1_1") (pintype "passive"))
    )
    (net (code "49") (name "Net-(C7-Pad1)") (class "Default")
      (node (ref "C7") (pin "1") (pinfunction "1_1") (pintype "passive"))
      (node (ref "R60") (pin "1") (pinfunction "1_1") (pintype "passive"))
    )
    (net (code "50") (name "Net-(C11-Pad1)") (class "Default")
      (node (ref "C11") (pin "1") (pinfunction "1_1") (pintype "passive"))
      (node (ref "R47") (pin "1") (pinfunction "1_1") (pintype "passive"))
    )
    (net (code "51") (name "Net-(C15-Pad1)") (class "Default")
      (node (ref "C15") (pin "1") (pinfunction "1_1") (pintype "passive"))
      (node (ref "R56") (pin "1") (pinfunction "1_1") (pintype "passive"))
    )
    (net (code "52") (name "Net-(C17-Pad1)") (class "Default")
      (node (ref "C17") (pin "1") (pinfunction "1_1") (pintype "passive"))
      (node (ref "R85") (pin "1") (pinfunction "1_1") (pintype "passive"))
    )
    (net (code "53") (name "Net-(C19-Pad1)") (class "Default")
      (node (ref "C19") (pin "1") (pinfunction "1_1") (pintype "passive"))
      (node (ref "R90") (pin "1") (pinfunction "1_1") (pintype "passive"))
    )
    (net (code "54") (name "Net-(CLAMP_REF-A)") (class "Default")
      (node (ref "CLAMP_REF") (pin "1") (pinfunction "A_1") (pintype "passive"))
      (node (ref "R63") (pin "2") (pinfunction "2_2") (pintype "passive"))
    )
    (net (code "55") (name "Net-(CLAMP_REF-E)") (class "Default")
      (node (ref "CLAMP_REF") (pin "3") (pinfunction "E_3") (pintype "passive"))
      (node (ref "R62") (pin "1") (pinfunction "1_1") (pintype "passive"))
    )
    (net (code "56") (name "Net-(CLAMP_REF-S)") (class "Default")
      (node (ref "C10") (pin "1") (pinfunction "1_1") (pintype "passive"))
      (node (ref "CLAMP_REF") (pin "2") (pinfunction "S_2") (pintype "passive"))
      (node (ref "IC4") (pin "3") (pinfunction "+IN_3") (pintype "input"))
    )
    (net (code "57") (name "Net-(D1-K1)") (class "Default")
      (node (ref "D1") (pin "1") (pinfunction "K1_1") (pintype "passive"))
      (node (ref "IC2") (pin "6") (pinfunction "CTRL_6") (pintype "input"))
      (node (ref "R44") (pin "1") (pinfunction "1_1") (pintype "passive"))
    )
    (net (code "58") (name "Net-(D1-K2)") (class "Default")
      (node (ref "D1") (pin "2") (pinfunction "K2_2") (pintype "passive"))
      (node (ref "IC2") (pin "11") (pinfunction "CTRL_11") (pintype "input"))
      (node (ref "R51") (pin "1") (pinfunction "1_1") (pintype "passive"))
    )
    (net (code "59") (name "Net-(D2-K1)") (class "Default")
      (node (ref "D2") (pin "1") (pinfunction "K1_1") (pintype "passive"))
      (node (ref "IC6") (pin "6") (pinfunction "CTRL_6") (pintype "input"))
      (node (ref "R70") (pin "1") (pinfunction "1_1") (pintype "passive"))
    )
    (net (code "60") (name "Net-(D2-K2)") (class "Default")
      (node (ref "D2") (pin "2") (pinfunction "K2_2") (pintype "passive"))
      (node (ref "IC6") (pin "11") (pinfunction "CTRL_11") (pintype "input"))
      (node (ref "R69") (pin "1") (pinfunction "1_1") (pintype "passive"))
    )
    (net (code "61") (name "Net-(D3-C1A2)") (class "Default")
      (node (ref "D3") (pin "3") (pinfunction "C1A2_3") (pintype "passive"))
      (node (ref "IC1") (pin "8") (pinfunction "OUT_8") (pintype "output"))
      (node (ref "R4") (pin "2") (pinfunction "2_2") (pintype "passive"))
    )
    (net (code "62") (name "Net-(D4-C1A2)") (class "Default")
      (node (ref "D4") (pin "3") (pinfunction "C1A2_3") (pintype "passive"))
      (node (ref "IC9") (pin "8") (pinfunction "OUT_8") (pintype "output"))
      (node (ref "R79") (pin "2") (pinfunction "2_2") (pintype "passive"))
    )
    (net (code "63") (name "Net-(D5-C1A2)") (class "Default")
      (node (ref "D5") (pin "3") (pinfunction "C1A2_3") (pintype "passive"))
      (node (ref "IC1") (pin "14") (pinfunction "OUT_14") (pintype "output"))
      (node (ref "R21") (pin "2") (pinfunction "2_2") (pintype "passive"))
    )
    (net (code "64") (name "Net-(D6-C1A2)") (class "Default")
      (node (ref "D6") (pin "3") (pinfunction "C1A2_3") (pintype "passive"))
      (node (ref "IC9") (pin "14") (pinfunction "OUT_14") (pintype "output"))
      (node (ref "R76") (pin "2") (pinfunction "2_2") (pintype "passive"))
    )
    (net (code "65") (name "Net-(IC1A--IN)") (class "Default")
      (node (ref "IC1") (pin "1") (pinfunction "OUT_1") (pintype "output"))
      (node (ref "IC1") (pin "2") (pinfunction "-IN_2") (pintype "input"))
      (node (ref "R12") (pin "1") (pinfunction "1_1") (pintype "passive"))
      (node (ref "R3") (pin "1") (pinfunction "1_1") (pintype "passive"))
    )
    (net (code "66") (name "Net-(IC1B--IN)") (class "Default")
      (node (ref "IC1") (pin "6") (pinfunction "-IN_6") (pintype "input"))
      (node (ref "IC1") (pin "7") (pinfunction "OUT_7") (pintype "output"))
      (node (ref "R22") (pin "1") (pinfunction "1_1") (pintype "passive"))
      (node (ref "R31") (pin "1") (pinfunction "1_1") (pintype "passive"))
    )
    (net (code "67") (name "Net-(IC1C--IN)") (class "Default")
      (node (ref "IC1") (pin "9") (pinfunction "-IN_9") (pintype "input"))
      (node (ref "R3") (pin "2") (pinfunction "2_2") (pintype "passive"))
      (node (ref "R4") (pin "1") (pinfunction "1_1") (pintype "passive"))
      (node (ref "R53") (pin "2") (pinfunction "2_2") (pintype "passive"))
      (node (ref "R8") (pin "1") (pinfunction "1_1") (pintype "passive"))
    )
    (net (code "68") (name "Net-(IC1D--IN)") (class "Default")
      (node (ref "IC1") (pin "13") (pinfunction "-IN_13") (pintype "input"))
      (node (ref "R14") (pin "1") (pinfunction "1_1") (pintype "passive"))
      (node (ref "R21") (pin "1") (pinfunction "1_1") (pintype "passive"))
      (node (ref "R31") (pin "2") (pinfunction "2_2") (pintype "passive"))
    )
    (net (code "69") (name "Net-(IC2A-IN)") (class "Default")
      (node (ref "IC2") (pin "2") (pinfunction "IN_2") (pintype "input"))
      (node (ref "R34") (pin "2") (pinfunction "2_2") (pintype "passive"))
      (node (ref "R35") (pin "2") (pinfunction "2_2") (pintype "passive"))
    )
    (net (code "70") (name "Net-(IC2A-OUT)") (class "Default")
      (node (ref "C13") (pin "2") (pinfunction "2_2") (pintype "passive"))
      (node (ref "IC2") (pin "4") (pinfunction "OUT_4") (pintype "output"))
      (node (ref "IC7") (pin "9") (pinfunction "-IN_9") (pintype "input"))
      (node (ref "R33") (pin "1") (pinfunction "1_1") (pintype "passive"))
    )
    (net (code "71") (name "Net-(IC2B-IN)") (class "Default")
      (node (ref "IC2") (pin "7") (pinfunction "IN_7") (pintype "input"))
      (node (ref "R5") (pin "2") (pinfunction "2_2") (pintype "passive"))
      (node (ref "R6") (pin "2") (pinfunction "2_2") (pintype "passive"))
    )
    (net (code "72") (name "Net-(IC2B-OUT)") (class "Default")
      (node (ref "C4") (pin "2") (pinfunction "2_2") (pintype "passive"))
      (node (ref "IC2") (pin "5") (pinfunction "OUT_5") (pintype "output"))
      (node (ref "IC5") (pin "6") (pinfunction "-IN_6") (pintype "input"))
      (node (ref "R10") (pin "1") (pinfunction "1_1") (pintype "passive"))
    )
    (net (code "73") (name "Net-(IC2C-IN)") (class "Default")
      (node (ref "IC2") (pin "10") (pinfunction "IN_10") (pintype "input"))
      (node (ref "R11") (pin "2") (pinfunction "2_2") (pintype "passive"))
      (node (ref "R7") (pin "2") (pinfunction "2_2") (pintype "passive"))
    )
    (net (code "74") (name "Net-(IC2C-OUT)") (class "Default")
      (node (ref "C12") (pin "2") (pinfunction "2_2") (pintype "passive"))
      (node (ref "IC2") (pin "12") (pinfunction "OUT_12") (pintype "output"))
      (node (ref "IC5") (pin "9") (pinfunction "-IN_9") (pintype "input"))
      (node (ref "R36") (pin "1") (pinfunction "1_1") (pintype "passive"))
    )
    (net (code "75") (name "Net-(IC2D-IN)") (class "Default")
      (node (ref "IC2") (pin "15") (pinfunction "IN_15") (pintype "input"))
      (node (ref "R59") (pin "2") (pinfunction "2_2") (pintype "passive"))
      (node (ref "R60") (pin "2") (pinfunction "2_2") (pintype "passive"))
    )
    (net (code "76") (name "Net-(IC2D-OUT)") (class "Default")
      (node (ref "C6") (pin "2") (pinfunction "2_2") (pintype "passive"))
      (node (ref "IC2") (pin "13") (pinfunction "OUT_13") (pintype "output"))
      (node (ref "IC7") (pin "13") (pinfunction "-IN_13") (pintype "input"))
      (node (ref "R58") (pin "1") (pinfunction "1_1") (pintype "passive"))
    )
    (net (code "77") (name "Net-(IC2E-MODE)") (class "Default")
      (node (ref "IC2") (pin "1") (pinfunction "MODE_1") (pintype "input"))
      (node (ref "R94") (pin "1") (pinfunction "1_1") (pintype "passive"))
    )
    (net (code "78") (name "Net-(IC3A--IN)") (class "Default")
      (node (ref "IC3") (pin "2") (pinfunction "-IN_2") (pintype "input"))
      (node (ref "R9") (pin "2") (pinfunction "2_2") (pintype "passive"))
    )
    (net (code "79") (name "Net-(IC3A-OUT)") (class "Default")
      (node (ref "IC3") (pin "1") (pinfunction "OUT_1") (pintype "output"))
      (node (ref "R24") (pin "2") (pinfunction "2_2") (pintype "passive"))
    )
    (net (code "80") (name "Net-(IC3B--IN)") (class "Default")
      (node (ref "IC3") (pin "6") (pinfunction "-IN_6") (pintype "input"))
      (node (ref "R48") (pin "1") (pinfunction "1_1") (pintype "passive"))
    )
    (net (code "81") (name "Net-(IC3B-OUT)") (class "Default")
      (node (ref "IC3") (pin "7") (pinfunction "OUT_7") (pintype "output"))
      (node (ref "R57") (pin "2") (pinfunction "2_2") (pintype "passive"))
    )
    (net (code "82") (name "Net-(IC3C--IN)") (class "Default")
      (node (ref "IC3") (pin "9") (pinfunction "-IN_9") (pintype "input"))
      (node (ref "R104") (pin "2") (pinfunction "2_2") (pintype "passive"))
    )
    (net (code "83") (name "Net-(IC3C-OUT)") (class "Default")
      (node (ref "IC3") (pin "8") (pinfunction "OUT_8") (pintype "output"))
      (node (ref "R105") (pin "1") (pinfunction "1_1") (pintype "passive"))
    )
    (net (code "84") (name "Net-(IC3D--IN)") (class "Default")
      (node (ref "IC3") (pin "13") (pinfunction "-IN_13") (pintype "input"))
      (node (ref "R109") (pin "1") (pinfunction "1_1") (pintype "passive"))
    )
    (net (code "85") (name "Net-(IC3D-OUT)") (class "Default")
      (node (ref "IC3") (pin "14") (pinfunction "OUT_14") (pintype "output"))
      (node (ref "R111") (pin "1") (pinfunction "1_1") (pintype "passive"))
    )
    (net (code "86") (name "Net-(IC4B-+IN)") (class "Default")
      (node (ref "C1") (pin "1") (pinfunction "1_1") (pintype "passive"))
      (node (ref "IC4") (pin "5") (pinfunction "+IN_5") (pintype "input"))
      (node (ref "OFFSET_LINA") (pin "2") (pinfunction "S_2") (pintype "passive"))
    )
    (net (code "87") (name "Net-(IC5B-OUT)") (class "Default")
      (node (ref "C4") (pin "1") (pinfunction "1_1") (pintype "passive"))
      (node (ref "IC5") (pin "7") (pinfunction "OUT_7") (pintype "output"))
      (node (ref "R10") (pin "2") (pinfunction "2_2") (pintype "passive"))
      (node (ref "R20") (pin "1") (pinfunction "1_1") (pintype "passive"))
      (node (ref "R48") (pin "2") (pinfunction "2_2") (pintype "passive"))
    )
    (net (code "88") (name "Net-(IC5C-OUT)") (class "Default")
      (node (ref "C12") (pin "1") (pinfunction "1_1") (pintype "passive"))
      (node (ref "IC5") (pin "8") (pinfunction "OUT_8") (pintype "output"))
      (node (ref "R29") (pin "1") (pinfunction "1_1") (pintype "passive"))
      (node (ref "R36") (pin "2") (pinfunction "2_2") (pintype "passive"))
      (node (ref "R9") (pin "1") (pinfunction "1_1") (pintype "passive"))
    )
    (net (code "89") (name "Net-(IC5D--IN)") (class "Default")
      (node (ref "IC5") (pin "13") (pinfunction "-IN_13") (pintype "input"))
      (node (ref "R28") (pin "1") (pinfunction "1_1") (pintype "passive"))
      (node (ref "R29") (pin "2") (pinfunction "2_2") (pintype "passive"))
    )
    (net (code "90") (name "Net-(IC5D-OUT)") (class "Default")
      (node (ref "1K") (pin "1") (pinfunction "1_1") (pintype "passive"))
      (node (ref "IC5") (pin "14") (pinfunction "OUT_14") (pintype "output"))
      (node (ref "R28") (pin "2") (pinfunction "2_2") (pintype "passive"))
    )
    (net (code "91") (name "Net-(IC6A-IN)") (class "Default")
      (node (ref "IC6") (pin "2") (pinfunction "IN_2") (pintype "input"))
      (node (ref "R89") (pin "2") (pinfunction "2_2") (pintype "passive"))
      (node (ref "R90") (pin "2") (pinfunction "2_2") (pintype "passive"))
    )
    (net (code "92") (name "Net-(IC6B-IN)") (class "Default")
      (node (ref "IC6") (pin "7") (pinfunction "IN_7") (pintype "input"))
      (node (ref "R54") (pin "2") (pinfunction "2_2") (pintype "passive"))
      (node (ref "R56") (pin "2") (pinfunction "2_2") (pintype "passive"))
    )
    (net (code "93") (name "Net-(IC6B-OUT)") (class "Default")
      (node (ref "C16") (pin "2") (pinfunction "2_2") (pintype "passive"))
      (node (ref "IC6") (pin "5") (pinfunction "OUT_5") (pintype "output"))
      (node (ref "IC8") (pin "6") (pinfunction "-IN_6") (pintype "input"))
      (node (ref "R64") (pin "1") (pinfunction "1_1") (pintype "passive"))
    )
    (net (code "94") (name "Net-(IC6C-IN)") (class "Default")
      (node (ref "IC6") (pin "10") (pinfunction "IN_10") (pintype "input"))
      (node (ref "R45") (pin "2") (pinfunction "2_2") (pintype "passive"))
      (node (ref "R47") (pin "2") (pinfunction "2_2") (pintype "passive"))
    )
    (net (code "95") (name "Net-(IC6C-OUT)") (class "Default")
      (node (ref "C14") (pin "2") (pinfunction "2_2") (pintype "passive"))
      (node (ref "IC6") (pin "12") (pinfunction "OUT_12") (pintype "output"))
      (node (ref "IC8") (pin "9") (pinfunction "-IN_9") (pintype "input"))
      (node (ref "R49") (pin "1") (pinfunction "1_1") (pintype "passive"))
    )
    (net (code "96") (name "Net-(IC6D-IN)") (class "Default")
      (node (ref "IC6") (pin "15") (pinfunction "IN_15") (pintype "input"))
      (node (ref "R84") (pin "2") (pinfunction "2_2") (pintype "passive"))
      (node (ref "R85") (pin "2") (pinfunction "2_2") (pintype "passive"))
    )
    (net (code "97") (name "Net-(IC6E-MODE)") (class "Default")
      (node (ref "IC6") (pin "1") (pinfunction "MODE_1") (pintype "input"))
      (node (ref "R110") (pin "1") (pinfunction "1_1") (pintype "passive"))
    )
    (net (code "98") (name "Net-(IC7A-+IN)") (class "Default")
      (node (ref "IC7") (pin "3") (pinfunction "+IN_3") (pintype "input"))
      (node (ref "R32") (pin "2") (pinfunction "2_2") (pintype "passive"))
    )
    (net (code "99") (name "Net-(IC7A--IN)") (class "Default")
      (node (ref "IC7") (pin "1") (pinfunction "OUT_1") (pintype "output"))
      (node (ref "IC7") (pin "2") (pinfunction "-IN_2") (pintype "input"))
      (node (ref "R33") (pin "2") (pinfunction "2_2") (pintype "passive"))
    )
    (net (code "100") (name "Net-(IC7B--IN)") (class "Default")
      (node (ref "IC7") (pin "6") (pinfunction "-IN_6") (pintype "input"))
      (node (ref "R18") (pin "1") (pinfunction "1_1") (pintype "passive"))
      (node (ref "R55") (pin "2") (pinfunction "2_2") (pintype "passive"))
    )
    (net (code "101") (name "Net-(IC7B-OUT)") (class "Default")
      (node (ref "IC7") (pin "7") (pinfunction "OUT_7") (pintype "output"))
      (node (ref "R18") (pin "2") (pinfunction "2_2") (pintype "passive"))
      (node (ref "R58") (pin "2") (pinfunction "2_2") (pintype "passive"))
    )
    (net (code "102") (name "Net-(IC8B-OUT)") (class "Default")
      (node (ref "C16") (pin "1") (pinfunction "1_1") (pintype "passive"))
      (node (ref "IC8") (pin "7") (pinfunction "OUT_7") (pintype "output"))
      (node (ref "R109") (pin "2") (pinfunction "2_2") (pintype "passive"))
      (node (ref "R64") (pin "2") (pinfunction "2_2") (pintype "passive"))
      (node (ref "R66") (pin "1") (pinfunction "1_1") (pintype "passive"))
    )
    (net (code "103") (name "Net-(IC8C-OUT)") (class "Default")
      (node (ref "C14") (pin "1") (pinfunction "1_1") (pintype "passive"))
      (node (ref "IC8") (pin "8") (pinfunction "OUT_8") (pintype "output"))
      (node (ref "R104") (pin "1") (pinfunction "1_1") (pintype "passive"))
      (node (ref "R49") (pin "2") (pinfunction "2_2") (pintype "passive"))
      (node (ref "R68") (pin "1") (pinfunction "1_1") (pintype "passive"))
    )
    (net (code "104") (name "Net-(IC8D--IN)") (class "Default")
      (node (ref "IC8") (pin "13") (pinfunction "-IN_13") (pintype "input"))
      (node (ref "R67") (pin "1") (pinfunction "1_1") (pintype "passive"))
      (node (ref "R68") (pin "2") (pinfunction "2_2") (pintype "passive"))
    )
    (net (code "105") (name "Net-(IC8D-OUT)") (class "Default")
      (node (ref "1K1") (pin "1") (pinfunction "1_1") (pintype "passive"))
      (node (ref "IC8") (pin "14") (pinfunction "OUT_14") (pintype "output"))
      (node (ref "R67") (pin "2") (pinfunction "2_2") (pintype "passive"))
    )
    (net (code "106") (name "Net-(IC9A--IN)") (class "Default")
      (node (ref "IC9") (pin "1") (pinfunction "OUT_1") (pintype "output"))
      (node (ref "IC9") (pin "2") (pinfunction "-IN_2") (pintype "input"))
      (node (ref "R78") (pin "1") (pinfunction "1_1") (pintype "passive"))
      (node (ref "R80") (pin "1") (pinfunction "1_1") (pintype "passive"))
    )
    (net (code "107") (name "Net-(IC9B--IN)") (class "Default")
      (node (ref "IC9") (pin "6") (pinfunction "-IN_6") (pintype "input"))
      (node (ref "IC9") (pin "7") (pinfunction "OUT_7") (pintype "output"))
      (node (ref "R75") (pin "1") (pinfunction "1_1") (pintype "passive"))
      (node (ref "R77") (pin "1") (pinfunction "1_1") (pintype "passive"))
    )
    (net (code "108") (name "Net-(IC9C--IN)") (class "Default")
      (node (ref "IC9") (pin "9") (pinfunction "-IN_9") (pintype "input"))
      (node (ref "R73") (pin "2") (pinfunction "2_2") (pintype "passive"))
      (node (ref "R78") (pin "2") (pinfunction "2_2") (pintype "passive"))
      (node (ref "R79") (pin "1") (pinfunction "1_1") (pintype "passive"))
      (node (ref "R81") (pin "1") (pinfunction "1_1") (pintype "passive"))
    )
    (net (code "109") (name "Net-(IC9D--IN)") (class "Default")
      (node (ref "IC9") (pin "13") (pinfunction "-IN_13") (pintype "input"))
      (node (ref "R75") (pin "2") (pinfunction "2_2") (pintype "passive"))
      (node (ref "R76") (pin "1") (pinfunction "1_1") (pintype "passive"))
      (node (ref "R82") (pin "1") (pinfunction "1_1") (pintype "passive"))
    )
    (net (code "110") (name "Net-(IC10A-+IN)") (class "Default")
      (node (ref "IC10") (pin "3") (pinfunction "+IN_3") (pintype "input"))
      (node (ref "R16") (pin "2") (pinfunction "2_2") (pintype "passive"))
    )
    (net (code "111") (name "Net-(IC10A--IN)") (class "Default")
      (node (ref "IC10") (pin "1") (pinfunction "OUT_1") (pintype "output"))
      (node (ref "IC10") (pin "2") (pinfunction "-IN_2") (pintype "input"))
      (node (ref "R83") (pin "2") (pinfunction "2_2") (pintype "passive"))
    )
    (net (code "112") (name "Net-(IC10B--IN)") (class "Default")
      (node (ref "IC10") (pin "6") (pinfunction "-IN_6") (pintype "input"))
      (node (ref "R87") (pin "2") (pinfunction "2_2") (pintype "passive"))
      (node (ref "R92") (pin "1") (pinfunction "1_1") (pintype "passive"))
    )
    (net (code "113") (name "Net-(IC10B-OUT)") (class "Default")
      (node (ref "IC10") (pin "7") (pinfunction "OUT_7") (pintype "output"))
      (node (ref "R88") (pin "2") (pinfunction "2_2") (pintype "passive"))
      (node (ref "R92") (pin "2") (pinfunction "2_2") (pintype "passive"))
    )
    (net (code "114") (name "Net-(IC10C--IN)") (class "Default")
      (node (ref "C8") (pin "2") (pinfunction "2_2") (pintype "passive"))
      (node (ref "IC10") (pin "9") (pinfunction "-IN_9") (pintype "input"))
      (node (ref "IC6") (pin "13") (pinfunction "OUT_13") (pintype "output"))
      (node (ref "R83") (pin "1") (pinfunction "1_1") (pintype "passive"))
    )
    (net (code "115") (name "Net-(IC10D--IN)") (class "Default")
      (node (ref "C18") (pin "2") (pinfunction "2_2") (pintype "passive"))
      (node (ref "IC10") (pin "13") (pinfunction "-IN_13") (pintype "input"))
      (node (ref "IC6") (pin "4") (pinfunction "OUT_4") (pintype "output"))
      (node (ref "R88") (pin "1") (pinfunction "1_1") (pintype "passive"))
    )
    (net (code "116") (name "Net-(IC12A--IN)") (class "Default")
      (node (ref "IC12") (pin "2") (pinfunction "-IN_2") (pintype "input"))
      (node (ref "R100") (pin "2") (pinfunction "2_2") (pintype "passive"))
      (node (ref "R101") (pin "1") (pinfunction "1_1") (pintype "passive"))
    )
    (net (code "117") (name "Net-(IC12A-OUT)") (class "Default")
      (node (ref "IC12") (pin "1") (pinfunction "OUT_1") (pintype "output"))
      (node (ref "R100") (pin "1") (pinfunction "1_1") (pintype "passive"))
      (node (ref "R102") (pin "2") (pinfunction "2_2") (pintype "passive"))
    )
    (net (code "118") (name "Net-(IC12B-+IN)") (class "Default")
      (node (ref "IC12") (pin "5") (pinfunction "+IN_5") (pintype "input"))
      (node (ref "R95") (pin "1") (pinfunction "1_1") (pintype "passive"))
      (node (ref "R96") (pin "1") (pinfunction "1_1") (pintype "passive"))
    )
    (net (code "119") (name "Net-(IC12B--IN)") (class "Default")
      (node (ref "IC12") (pin "6") (pinfunction "-IN_6") (pintype "input"))
      (node (ref "R102") (pin "1") (pinfunction "1_1") (pintype "passive"))
      (node (ref "R46") (pin "1") (pinfunction "1_1") (pintype "passive"))
      (node (ref "R99") (pin "2") (pinfunction "2_2") (pintype "passive"))
    )
    (net (code "120") (name "Net-(IC12C-+IN)") (class "Default")
      (node (ref "IC12") (pin "10") (pinfunction "+IN_10") (pintype "input"))
      (node (ref "R103") (pin "1") (pinfunction "1_1") (pintype "passive"))
      (node (ref "R98") (pin "1") (pinfunction "1_1") (pintype "passive"))
    )
    (net (code "121") (name "Net-(IC12C--IN)") (class "Default")
      (node (ref "IC12") (pin "9") (pinfunction "-IN_9") (pintype "input"))
      (node (ref "R107") (pin "1") (pinfunction "1_1") (pintype "passive"))
      (node (ref "R108") (pin "2") (pinfunction "2_2") (pintype "passive"))
      (node (ref "R97") (pin "1") (pinfunction "1_1") (pintype "passive"))
    )
    (net (code "122") (name "Net-(IC12D--IN)") (class "Default")
      (node (ref "IC12") (pin "13") (pinfunction "-IN_13") (pintype "input"))
      (node (ref "R113") (pin "1") (pinfunction "1_1") (pintype "passive"))
      (node (ref "R114") (pin "2") (pinfunction "2_2") (pintype "passive"))
    )
    (net (code "123") (name "Net-(IC14A--IN)") (class "Default")
      (node (ref "IC14") (pin "2") (pinfunction "-IN_2") (pintype "input"))
      (node (ref "R39") (pin "2") (pinfunction "2_2") (pintype "passive"))
      (node (ref "R42") (pin "1") (pinfunction "1_1") (pintype "passive"))
    )
    (net (code "124") (name "Net-(IC14A-OUT)") (class "Default")
      (node (ref "IC14") (pin "1") (pinfunction "OUT_1") (pintype "output"))
      (node (ref "R15") (pin "2") (pinfunction "2_2") (pintype "passive"))
      (node (ref "R39") (pin "1") (pinfunction "1_1") (pintype "passive"))
    )
    (net (code "125") (name "Net-(IC14B-+IN)") (class "Default")
      (node (ref "IC14") (pin "5") (pinfunction "+IN_5") (pintype "input"))
      (node (ref "R26") (pin "1") (pinfunction "1_1") (pintype "passive"))
      (node (ref "R27") (pin "1") (pinfunction "1_1") (pintype "passive"))
    )
    (net (code "126") (name "Net-(IC14B--IN)") (class "Default")
      (node (ref "IC14") (pin "6") (pinfunction "-IN_6") (pintype "input"))
      (node (ref "R106") (pin "1") (pinfunction "1_1") (pintype "passive"))
      (node (ref "R15") (pin "1") (pinfunction "1_1") (pintype "passive"))
      (node (ref "R38") (pin "2") (pinfunction "2_2") (pintype "passive"))
    )
    (net (code "127") (name "Net-(IC14C-+IN)") (class "Default")
      (node (ref "IC14") (pin "10") (pinfunction "+IN_10") (pintype "input"))
      (node (ref "R41") (pin "1") (pinfunction "1_1") (pintype "passive"))
      (node (ref "R43") (pin "1") (pinfunction "1_1") (pintype "passive"))
    )
    (net (code "128") (name "Net-(IC14C--IN)") (class "Default")
      (node (ref "IC14") (pin "9") (pinfunction "-IN_9") (pintype "input"))
      (node (ref "R19") (pin "2") (pinfunction "2_2") (pintype "passive"))
      (node (ref "R23") (pin "1") (pinfunction "1_1") (pintype "passive"))
      (node (ref "R40") (pin "1") (pinfunction "1_1") (pintype "passive"))
    )
    (net (code "129") (name "Net-(IC14D--IN)") (class "Default")
      (node (ref "IC14") (pin "13") (pinfunction "-IN_13") (pintype "input"))
      (node (ref "R17") (pin "1") (pinfunction "1_1") (pintype "passive"))
      (node (ref "R25") (pin "2") (pinfunction "2_2") (pintype "passive"))
    )
    (net (code "130") (name "Net-(LED_REF-E)") (class "Default")
      (node (ref "LED_REF") (pin "3") (pinfunction "E_3") (pintype "passive"))
      (node (ref "R112") (pin "1") (pinfunction "1_1") (pintype "passive"))
    )
    (net (code "131") (name "Net-(LED_REF-S)") (class "Default")
      (node (ref "C20") (pin "1") (pinfunction "1_1") (pintype "passive"))
      (node (ref "LED_REF") (pin "2") (pinfunction "S_2") (pintype "passive"))
      (node (ref "R113") (pin "2") (pinfunction "2_2") (pintype "passive"))
    )
    (net (code "132") (name "Net-(OFFSET_LINA-E)") (class "Default")
      (node (ref "OFFSET_LINA") (pin "3") (pinfunction "E_3") (pintype "passive"))
      (node (ref "R13") (pin "1") (pinfunction "1_1") (pintype "passive"))
    )
    (net (code "133") (name "Net-(OFFSET_REF-E)") (class "Default")
      (node (ref "OFFSET_REF") (pin "3") (pinfunction "E_3") (pintype "passive"))
      (node (ref "R2") (pin "1") (pinfunction "1_1") (pintype "passive"))
    )
    (net (code "134") (name "Net-(OFFSET_REF-S)") (class "Default")
      (node (ref "C9") (pin "1") (pinfunction "1_1") (pintype "passive"))
      (node (ref "OFFSET_REF") (pin "2") (pinfunction "S_2") (pintype "passive"))
      (node (ref "R17") (pin "2") (pinfunction "2_2") (pintype "passive"))
    )
    (net (code "135") (name "Net-(Q9-D)") (class "Default")
      (node (ref "JP8") (pin "1") (pinfunction "1_1") (pintype "passive"))
      (node (ref "JP8") (pin "2") (pinfunction "2_2") (pintype "passive"))
      (node (ref "Q9") (pin "3") (pinfunction "D_3") (pintype "passive"))
    )
    (net (code "136") (name "Net-(Q10-D)") (class "Default")
      (node (ref "JP8") (pin "10") (pinfunction "10_10") (pintype "passive"))
      (node (ref "JP8") (pin "9") (pinfunction "9_9") (pintype "passive"))
      (node (ref "Q10") (pin "3") (pinfunction "D_3") (pintype "passive"))
    )
    (net (code "137") (name "OFFSET_LIN") (class "Default")
      (node (ref "IC10") (pin "10") (pinfunction "+IN_10") (pintype "input"))
      (node (ref "IC10") (pin "12") (pinfunction "+IN_12") (pintype "input"))
      (node (ref "IC4") (pin "6") (pinfunction "-IN_6") (pintype "input"))
      (node (ref "IC4") (pin "7") (pinfunction "OUT_7") (pintype "output"))
      (node (ref "IC7") (pin "10") (pinfunction "+IN_10") (pintype "input"))
      (node (ref "IC7") (pin "12") (pinfunction "+IN_12") (pintype "input"))
    )
    (net (code "138") (name "OFFSET_REF") (class "Default")
      (node (ref "IC14") (pin "14") (pinfunction "OUT_14") (pintype "output"))
      (node (ref "R106") (pin "2") (pinfunction "2_2") (pintype "passive"))
      (node (ref "R23") (pin "2") (pinfunction "2_2") (pintype "passive"))
      (node (ref "R25") (pin "1") (pinfunction "1_1") (pintype "passive"))
      (node (ref "R46") (pin "2") (pinfunction "2_2") (pintype "passive"))
      (node (ref "R97") (pin "2") (pinfunction "2_2") (pintype "passive"))
    )
    (net (code "139") (name "OUT_A") (class "Default")
      (node (ref "1K") (pin "2") (pinfunction "2_2") (pintype "passive"))
      (node (ref "J2") (pin "1") (pinfunction "1_1") (pintype "passive"))
      (node (ref "JP7") (pin "1") (pinfunction "1_1") (pintype "passive"))
      (node (ref "OUT_A") (pin "P$3") (pinfunction "3_P$3") (pintype "passive"))
    )
    (net (code "140") (name "OUT_B") (class "Default")
      (node (ref "1K1") (pin "2") (pinfunction "2_2") (pintype "passive"))
      (node (ref "J2") (pin "5") (pinfunction "5_5") (pintype "passive"))
      (node (ref "JP7") (pin "5") (pinfunction "5_5") (pintype "passive"))
      (node (ref "OUT_B") (pin "P$3") (pinfunction "3_P$3") (pintype "passive"))
    )
    (net (code "141") (name "POT_EXPA_1") (class "Default")
      (node (ref "IC1") (pin "12") (pinfunction "+IN_12") (pintype "input"))
      (node (ref "JP2") (pin "4") (pinfunction "4_4") (pintype "passive"))
      (node (ref "JP3") (pin "4") (pinfunction "4_4") (pintype "passive"))
      (node (ref "POT_EXPA") (pin "1") (pinfunction "1_1") (pintype "bidirectional"))
      (node (ref "R22") (pin "2") (pinfunction "2_2") (pintype "passive"))
    )
    (net (code "142") (name "POT_EXPA_3") (class "Default")
      (node (ref "JP2") (pin "3") (pinfunction "3_3") (pintype "passive"))
      (node (ref "JP3") (pin "3") (pinfunction "3_3") (pintype "passive"))
      (node (ref "POT_EXPA") (pin "3") (pinfunction "3_3") (pintype "bidirectional"))
      (node (ref "R14") (pin "2") (pinfunction "2_2") (pintype "passive"))
    )
    (net (code "143") (name "POT_EXPB_1") (class "Default")
      (node (ref "IC9") (pin "12") (pinfunction "+IN_12") (pintype "input"))
      (node (ref "JP2") (pin "2") (pinfunction "2_2") (pintype "passive"))
      (node (ref "JP3") (pin "2") (pinfunction "2_2") (pintype "passive"))
      (node (ref "POT_EXPB") (pin "1") (pinfunction "1_1") (pintype "bidirectional"))
      (node (ref "R77") (pin "2") (pinfunction "2_2") (pintype "passive"))
    )
    (net (code "144") (name "POT_EXPB_3") (class "Default")
      (node (ref "JP2") (pin "1") (pinfunction "1_1") (pintype "passive"))
      (node (ref "JP3") (pin "1") (pinfunction "1_1") (pintype "passive"))
      (node (ref "POT_EXPB") (pin "3") (pinfunction "3_3") (pintype "bidirectional"))
      (node (ref "R82") (pin "2") (pinfunction "2_2") (pintype "passive"))
    )
    (net (code "145") (name "POT_LINA_1") (class "Default")
      (node (ref "IC1") (pin "10") (pinfunction "+IN_10") (pintype "input"))
      (node (ref "JP2") (pin "9") (pinfunction "9_9") (pintype "passive"))
      (node (ref "JP3") (pin "9") (pinfunction "9_9") (pintype "passive"))
      (node (ref "POT_LINA") (pin "1") (pinfunction "1_1") (pintype "bidirectional"))
      (node (ref "R12") (pin "2") (pinfunction "2_2") (pintype "passive"))
    )
    (net (code "146") (name "POT_LINA_3") (class "Default")
      (node (ref "JP2") (pin "8") (pinfunction "8_8") (pintype "passive"))
      (node (ref "JP3") (pin "8") (pinfunction "8_8") (pintype "passive"))
      (node (ref "POT_LINA") (pin "3") (pinfunction "3_3") (pintype "bidirectional"))
      (node (ref "R8") (pin "2") (pinfunction "2_2") (pintype "passive"))
    )
    (net (code "147") (name "POT_LINB_1") (class "Default")
      (node (ref "IC9") (pin "10") (pinfunction "+IN_10") (pintype "input"))
      (node (ref "JP2") (pin "7") (pinfunction "7_7") (pintype "passive"))
      (node (ref "JP3") (pin "7") (pinfunction "7_7") (pintype "passive"))
      (node (ref "POT_LINB") (pin "1") (pinfunction "1_1") (pintype "bidirectional"))
      (node (ref "R80") (pin "2") (pinfunction "2_2") (pintype "passive"))
    )
    (net (code "148") (name "POT_LINB_3") (class "Default")
      (node (ref "JP2") (pin "6") (pinfunction "6_6") (pintype "passive"))
      (node (ref "JP3") (pin "6") (pinfunction "6_6") (pintype "passive"))
      (node (ref "POT_LINB") (pin "3") (pinfunction "3_3") (pintype "bidirectional"))
      (node (ref "R81") (pin "2") (pinfunction "2_2") (pintype "passive"))
    )
    (net (code "149") (name "UNIPOLAR_A") (class "Default")
      (node (ref "JP1") (pin "1") (pinfunction "1_1") (pintype "passive"))
      (node (ref "JP6") (pin "1") (pinfunction "1_1") (pintype "passive"))
      (node (ref "R119") (pin "1") (pinfunction "1_1") (pintype "passive"))
      (node (ref "S1") (pin "3") (pinfunction "S_3") (pintype "passive"))
    )
    (net (code "150") (name "UNIPOLAR_B") (class "Default")
      (node (ref "JP1") (pin "4") (pinfunction "4_4") (pintype "passive"))
      (node (ref "JP6") (pin "4") (pinfunction "4_4") (pintype "passive"))
      (node (ref "R120") (pin "1") (pinfunction "1_1") (pintype "passive"))
      (node (ref "S2") (pin "3") (pinfunction "S_3") (pintype "passive"))
    )
    (net (code "151") (name "V_REF") (class "Default")
      (node (ref "IC13") (pin "1") (pinfunction "C_1") (pintype "passive"))
      (node (ref "R112") (pin "2") (pinfunction "2_2") (pintype "passive"))
      (node (ref "R13") (pin "2") (pinfunction "2_2") (pintype "passive"))
      (node (ref "R2") (pin "2") (pinfunction "2_2") (pintype "passive"))
      (node (ref "R37") (pin "2") (pinfunction "2_2") (pintype "passive"))
      (node (ref "R61") (pin "2") (pinfunction "2_2") (pintype "passive"))
      (node (ref "R62") (pin "2") (pinfunction "2_2") (pintype "passive"))
      (node (ref "R86") (pin "2") (pinfunction "2_2") (pintype "passive"))
      (node (ref "R91") (pin "2") (pinfunction "2_2") (pintype "passive"))
      (node (ref "R93") (pin "1") (pinfunction "1_1") (pintype "passive"))
    )
    (net (code "152") (name "unconnected-(S1-O-Pad1)") (class "Default")
      (node (ref "S1") (pin "1") (pinfunction "O_1") (pintype "passive"))
    )
    (net (code "153") (name "unconnected-(S2-O-Pad1)") (class "Default")
      (node (ref "S2") (pin "1") (pinfunction "O_1") (pintype "passive"))
    )
  )
)
